# RA6M1_2.net
KiCad netlist of a schematic drawn in Altium Designer
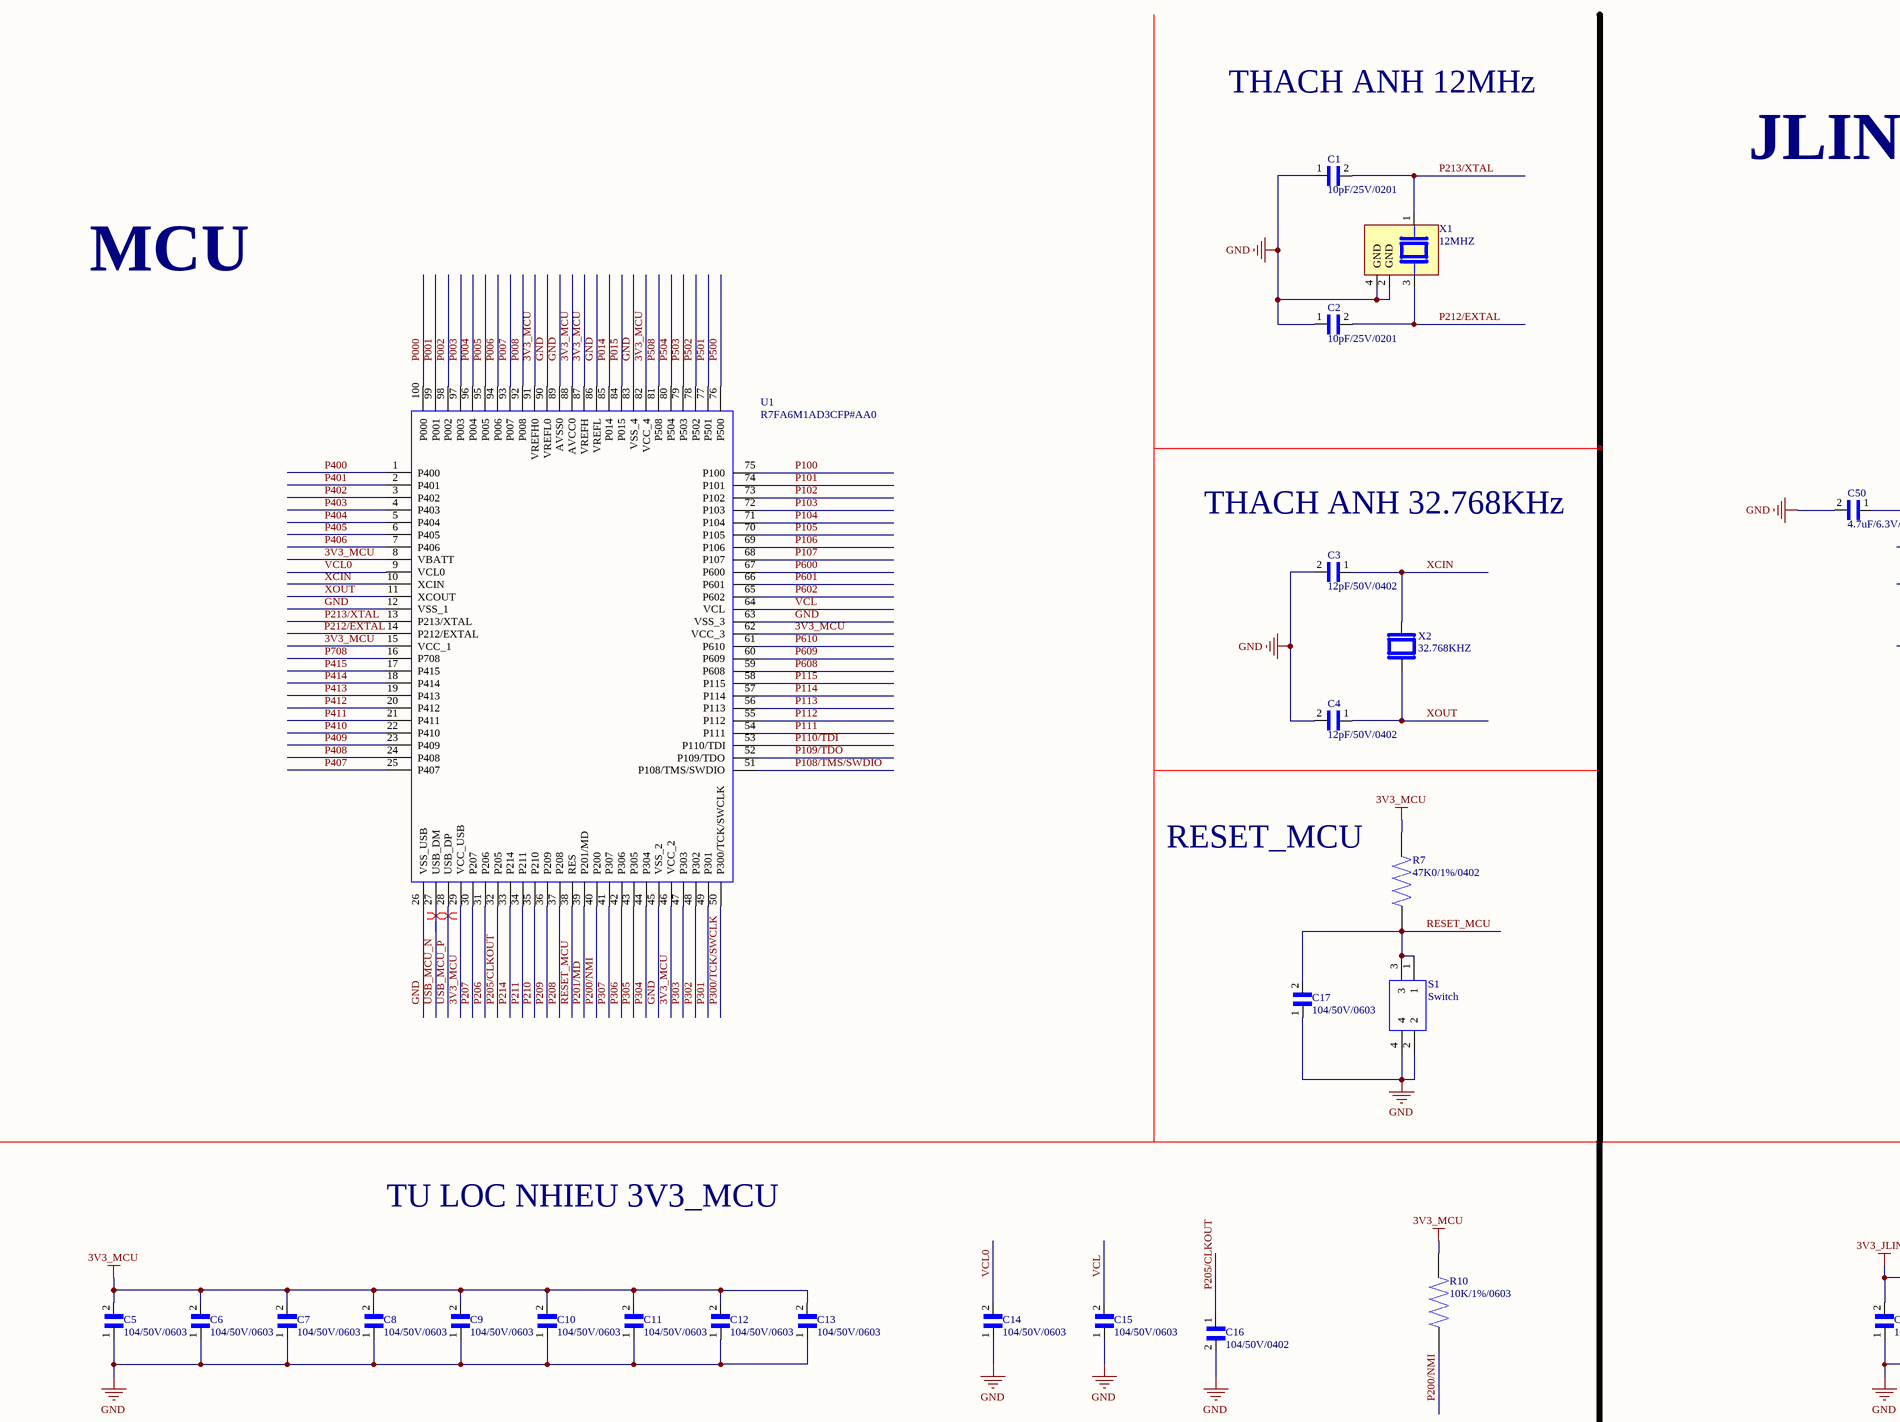
[diagram p0: RA6M1_2.SchDoc, top left]
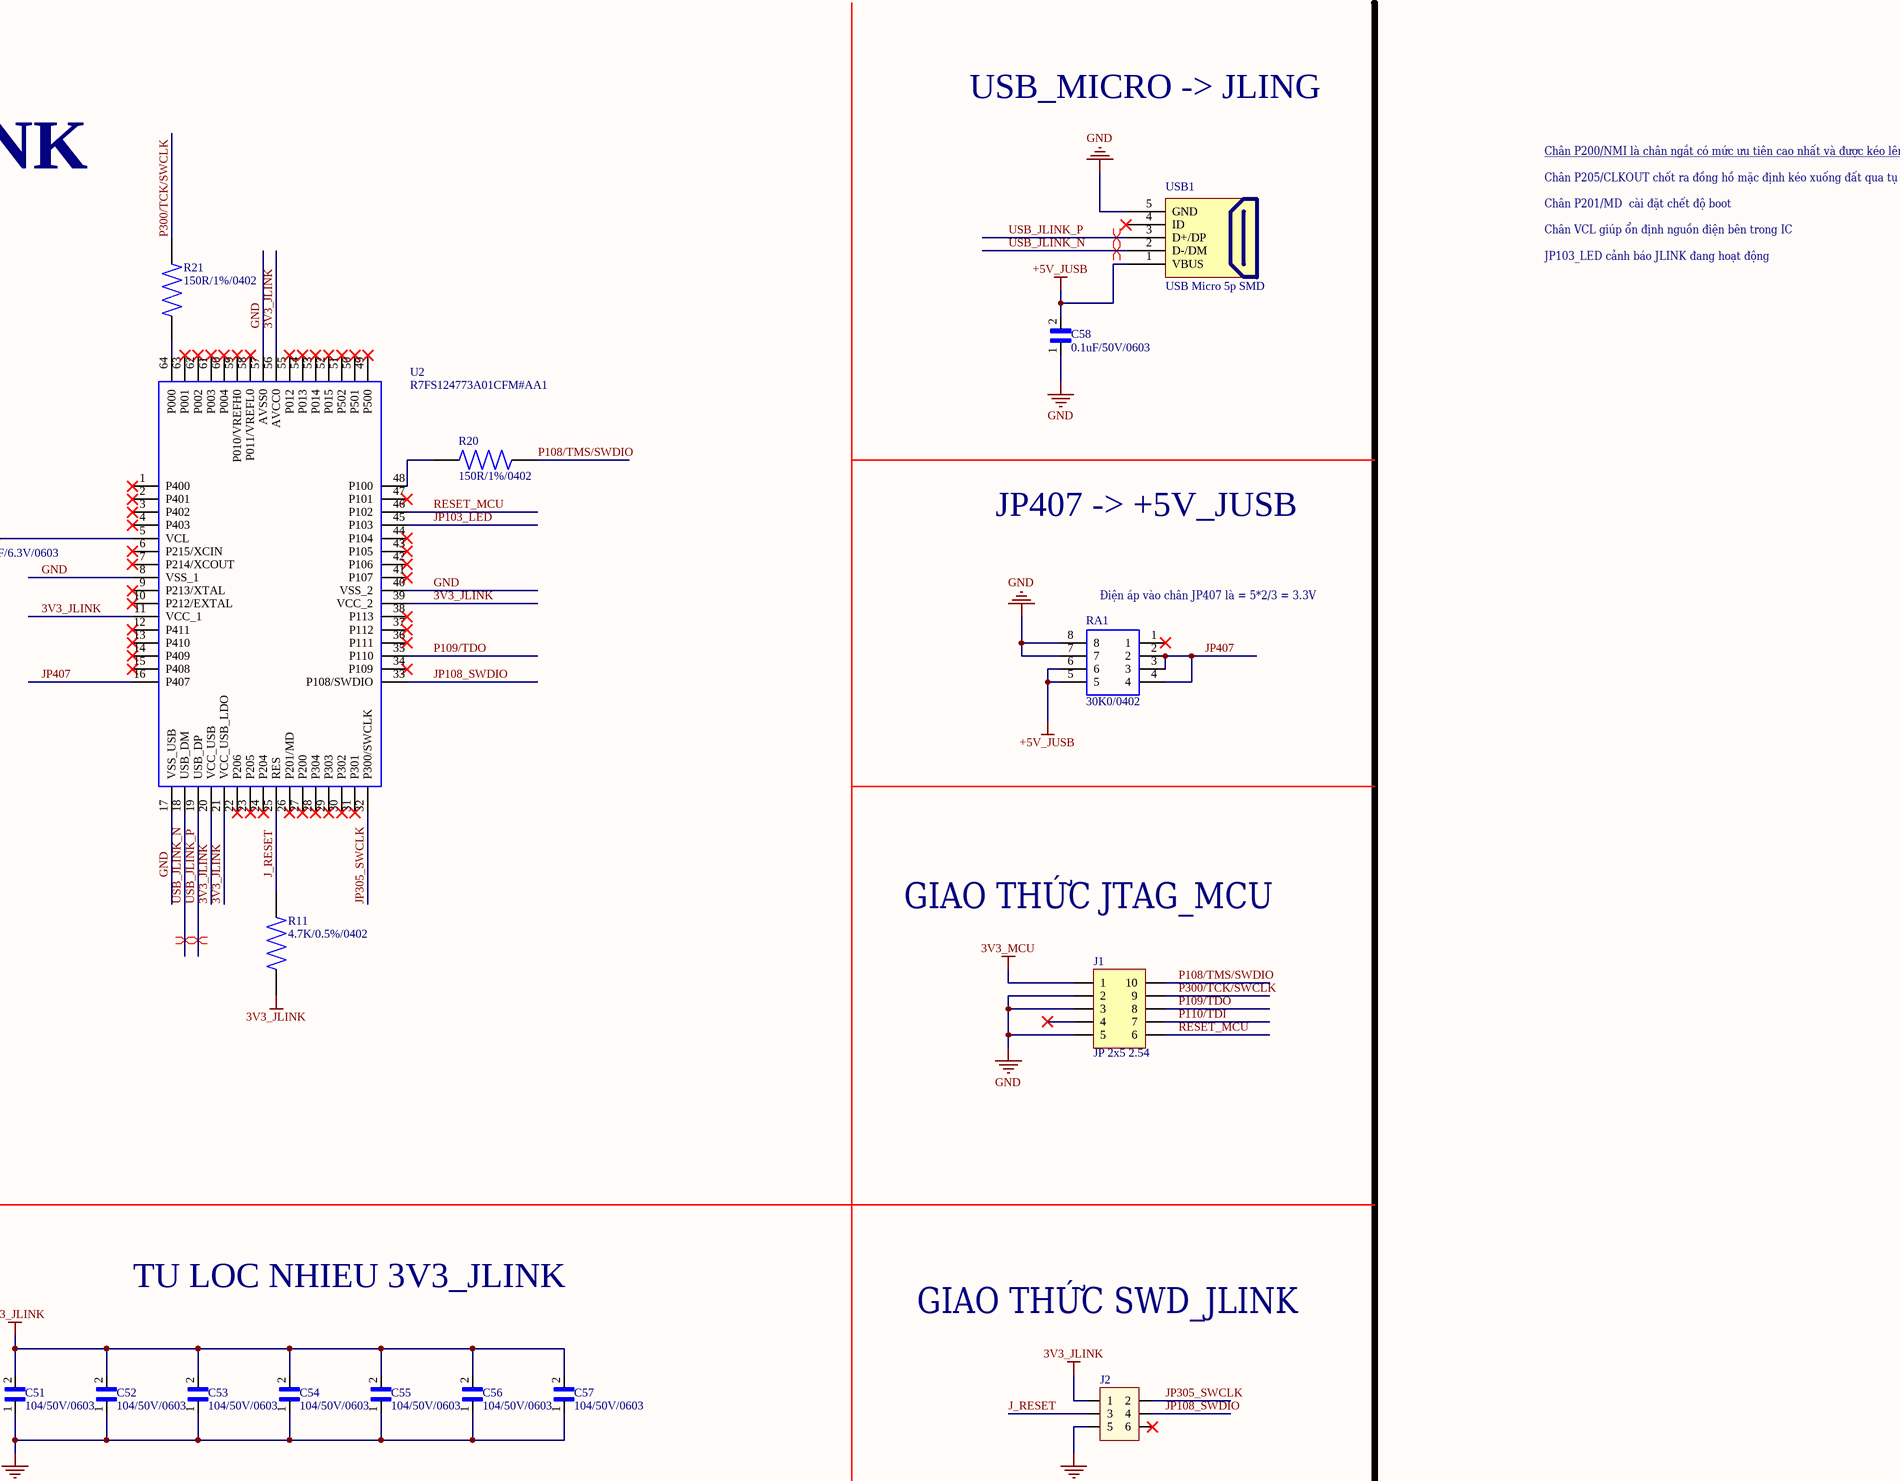
[diagram p1: RA6M1_2.SchDoc, top right]
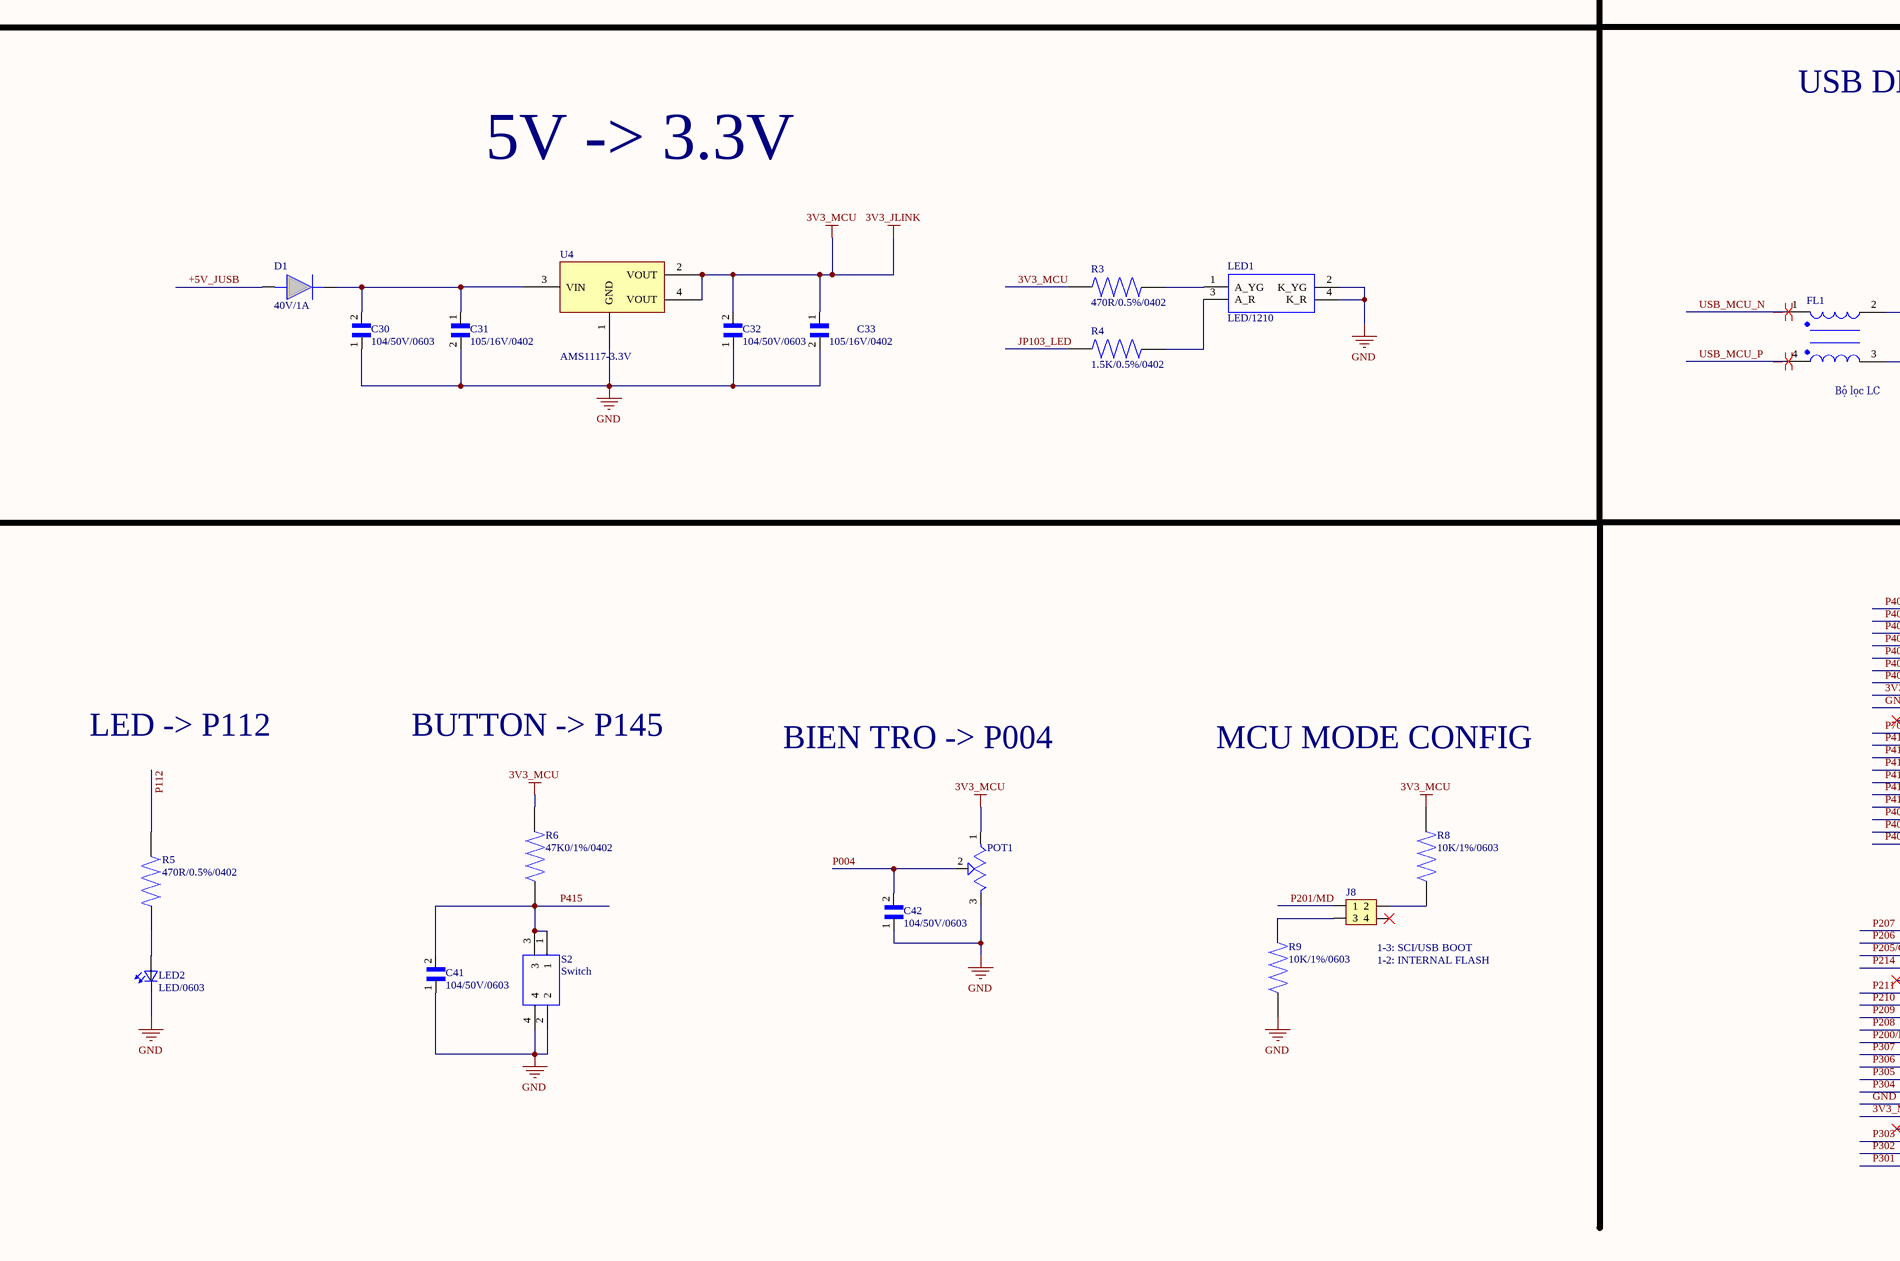
[diagram p2: RA6M1_2.SchDoc, bottom left]
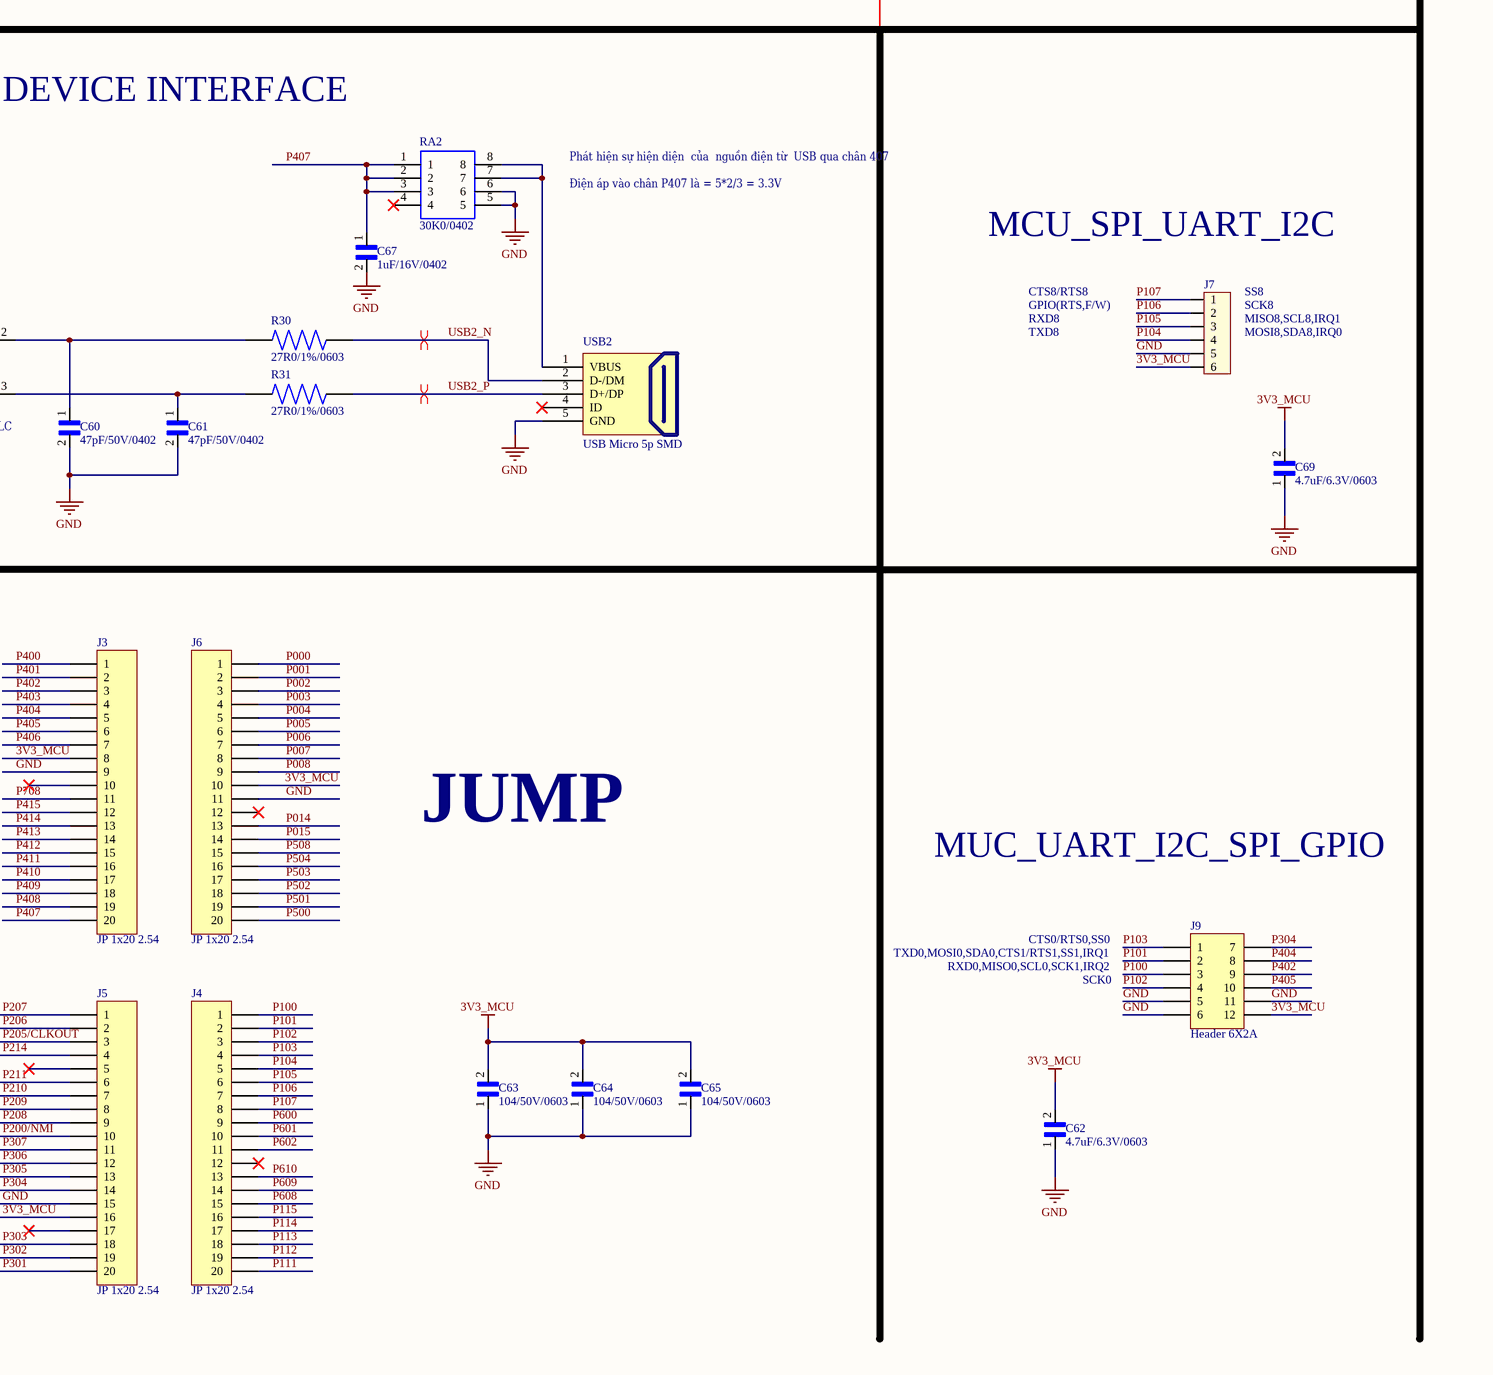
[diagram p3: RA6M1_2.SchDoc, bottom right]

(export (version "E")
  (design (tool "Eeschema 10.0.6"))
  (components
    (comp (ref "C1")
      (value "10pF/25V/0201")
      (footprint "RESC0603X26N")
      (description "TU0201")
      (fields (field (name "MP") "CL10B104KB8NNNC") (field (name "MF") "Samsung Electro-Mechanics"))
      (libsource (lib "Tu0201") (part "RESC0603X26N"))
    )
    (comp (ref "C2")
      (value "10pF/25V/0201")
      (footprint "RESC0603X26N")
      (description "TU0201")
      (fields (field (name "MP") "CL10B104KB8NNNC") (field (name "MF") "Samsung Electro-Mechanics"))
      (libsource (lib "Tu0201") (part "RESC0603X26N"))
    )
    (comp (ref "C3")
      (value "12pF/50V/0402")
      (footprint "CAPC1005X55N")
      (description "1ÂµF Â±10% 16V Ceramic Capacitor X5R 0402 (1005 Metric)")
      (fields (field (name "MP") "CL05A105KO5NNNC") (field (name "MF") "Samsung Electro-Mechanics"))
      (libsource (lib "RA6M1_DONE") (part "CL05A105KO5NNNC"))
    )
    (comp (ref "C4")
      (value "12pF/50V/0402")
      (footprint "CAPC1005X55N")
      (description "1ÂµF Â±10% 16V Ceramic Capacitor X5R 0402 (1005 Metric)")
      (fields (field (name "MP") "CL05A105KO5NNNC") (field (name "MF") "Samsung Electro-Mechanics"))
      (libsource (lib "RA6M1_DONE") (part "CL05A105KO5NNNC"))
    )
    (comp (ref "C5")
      (value "104/50V/0603")
      (footprint "CAPC1608X90N")
      (description "0.1ÂµF Â±10% 50V Ceramic Capacitor X7R 0603 _1608 Metric_")
      (fields (field (name "MP") "CL10B104KB8NNNC") (field (name "MF") "Samsung Electro-Mechanics"))
      (libsource (lib "RA6M1_DONE") (part "CL10B104KB8NNNC"))
    )
    (comp (ref "C6")
      (value "104/50V/0603")
      (footprint "CAPC1608X90N")
      (description "0.1ÂµF Â±10% 50V Ceramic Capacitor X7R 0603 _1608 Metric_")
      (fields (field (name "MP") "CL10B104KB8NNNC") (field (name "MF") "Samsung Electro-Mechanics"))
      (libsource (lib "RA6M1_DONE") (part "CL10B104KB8NNNC"))
    )
    (comp (ref "C7")
      (value "104/50V/0603")
      (footprint "CAPC1608X90N")
      (description "0.1ÂµF Â±10% 50V Ceramic Capacitor X7R 0603 _1608 Metric_")
      (fields (field (name "MP") "CL10B104KB8NNNC") (field (name "MF") "Samsung Electro-Mechanics"))
      (libsource (lib "RA6M1_DONE") (part "CL10B104KB8NNNC"))
    )
    (comp (ref "C8")
      (value "104/50V/0603")
      (footprint "CAPC1608X90N")
      (description "0.1ÂµF Â±10% 50V Ceramic Capacitor X7R 0603 _1608 Metric_")
      (fields (field (name "MP") "CL10B104KB8NNNC") (field (name "MF") "Samsung Electro-Mechanics"))
      (libsource (lib "RA6M1_DONE") (part "CL10B104KB8NNNC"))
    )
    (comp (ref "C9")
      (value "104/50V/0603")
      (footprint "CAPC1608X90N")
      (description "0.1ÂµF Â±10% 50V Ceramic Capacitor X7R 0603 _1608 Metric_")
      (fields (field (name "MP") "CL10B104KB8NNNC") (field (name "MF") "Samsung Electro-Mechanics"))
      (libsource (lib "RA6M1_DONE") (part "CL10B104KB8NNNC"))
    )
    (comp (ref "C10")
      (value "104/50V/0603")
      (footprint "CAPC1608X90N")
      (description "0.1ÂµF Â±10% 50V Ceramic Capacitor X7R 0603 _1608 Metric_")
      (fields (field (name "MP") "CL10B104KB8NNNC") (field (name "MF") "Samsung Electro-Mechanics"))
      (libsource (lib "RA6M1_DONE") (part "CL10B104KB8NNNC"))
    )
    (comp (ref "C11")
      (value "104/50V/0603")
      (footprint "CAPC1608X90N")
      (description "0.1ÂµF Â±10% 50V Ceramic Capacitor X7R 0603 _1608 Metric_")
      (fields (field (name "MP") "CL10B104KB8NNNC") (field (name "MF") "Samsung Electro-Mechanics"))
      (libsource (lib "RA6M1_DONE") (part "CL10B104KB8NNNC"))
    )
    (comp (ref "C12")
      (value "104/50V/0603")
      (footprint "CAPC1608X90N")
      (description "0.1ÂµF Â±10% 50V Ceramic Capacitor X7R 0603 _1608 Metric_")
      (fields (field (name "MP") "CL10B104KB8NNNC") (field (name "MF") "Samsung Electro-Mechanics"))
      (libsource (lib "RA6M1_DONE") (part "CL10B104KB8NNNC"))
    )
    (comp (ref "C13")
      (value "104/50V/0603")
      (footprint "CAPC1608X90N")
      (description "0.1ÂµF Â±10% 50V Ceramic Capacitor X7R 0603 _1608 Metric_")
      (fields (field (name "MP") "CL10B104KB8NNNC") (field (name "MF") "Samsung Electro-Mechanics"))
      (libsource (lib "RA6M1_DONE") (part "CL10B104KB8NNNC"))
    )
    (comp (ref "C14")
      (value "104/50V/0603")
      (footprint "CAPC1608X90N")
      (description "0.1ÂµF Â±10% 50V Ceramic Capacitor X7R 0603 _1608 Metric_")
      (fields (field (name "MP") "CL10B104KB8NNNC") (field (name "MF") "Samsung Electro-Mechanics"))
      (libsource (lib "RA6M1_DONE") (part "CL10B104KB8NNNC"))
    )
    (comp (ref "C15")
      (value "104/50V/0603")
      (footprint "CAPC1608X90N")
      (description "0.1ÂµF Â±10% 50V Ceramic Capacitor X7R 0603 _1608 Metric_")
      (fields (field (name "MP") "CL10B104KB8NNNC") (field (name "MF") "Samsung Electro-Mechanics"))
      (libsource (lib "RA6M1_DONE") (part "CL10B104KB8NNNC"))
    )
    (comp (ref "C16")
      (value "104/50V/0402")
      (footprint "CAPC1005X55N")
      (description "1ÂµF Â±10% 16V Ceramic Capacitor X5R 0402 (1005 Metric)")
      (fields (field (name "MP") "CL05A105KO5NNNC") (field (name "MF") "Samsung Electro-Mechanics"))
      (libsource (lib "") (part "CL05A105KO5NNNC_1"))
    )
    (comp (ref "C17")
      (value "104/50V/0603")
      (footprint "CAPC1608X90N")
      (description "0.1ÂµF Â±10% 50V Ceramic Capacitor X7R 0603 _1608 Metric_")
      (fields (field (name "MP") "CL10B104KB8NNNC") (field (name "MF") "Samsung Electro-Mechanics"))
      (libsource (lib "RA6M1_DONE") (part "CL10B104KB8NNNC"))
    )
    (comp (ref "C30")
      (value "104/50V/0603")
      (footprint "CAPC1608X90N")
      (description "0.1ÂµF Â±10% 50V Ceramic Capacitor X7R 0603 _1608 Metric_")
      (fields (field (name "MP") "CL10B104KB8NNNC") (field (name "MF") "Samsung Electro-Mechanics"))
      (libsource (lib "RA6M1_DONE") (part "CL10B104KB8NNNC"))
    )
    (comp (ref "C31")
      (value "105/16V/0402")
      (footprint "CAPC1005X55N")
      (description "1ÂµF Â±10% 16V Ceramic Capacitor X5R 0402 (1005 Metric)")
      (fields (field (name "MP") "CL05A105KO5NNNC") (field (name "MF") "Samsung Electro-Mechanics"))
      (libsource (lib "") (part "CL05A105KO5NNNC_1"))
    )
    (comp (ref "C32")
      (value "104/50V/0603")
      (footprint "CAPC1608X90N")
      (description "0.1ÂµF Â±10% 50V Ceramic Capacitor X7R 0603 _1608 Metric_")
      (fields (field (name "MP") "CL10B104KB8NNNC") (field (name "MF") "Samsung Electro-Mechanics"))
      (libsource (lib "RA6M1_DONE") (part "CL10B104KB8NNNC"))
    )
    (comp (ref "C33")
      (value "105/16V/0402")
      (footprint "CAPC1005X55N")
      (description "1ÂµF Â±10% 16V Ceramic Capacitor X5R 0402 (1005 Metric)")
      (fields (field (name "MP") "CL05A105KO5NNNC") (field (name "MF") "Samsung Electro-Mechanics"))
      (libsource (lib "") (part "CL05A105KO5NNNC_1"))
    )
    (comp (ref "C41")
      (value "104/50V/0603")
      (footprint "CAPC1608X90N")
      (description "0.1ÂµF Â±10% 50V Ceramic Capacitor X7R 0603 _1608 Metric_")
      (fields (field (name "MP") "CL10B104KB8NNNC") (field (name "MF") "Samsung Electro-Mechanics"))
      (libsource (lib "RA6M1_DONE") (part "CL10B104KB8NNNC"))
    )
    (comp (ref "C42")
      (value "104/50V/0603")
      (footprint "CAPC1608X90N")
      (description "0.1ÂµF Â±10% 50V Ceramic Capacitor X7R 0603 _1608 Metric_")
      (fields (field (name "MP") "CL10B104KB8NNNC") (field (name "MF") "Samsung Electro-Mechanics"))
      (libsource (lib "RA6M1_DONE") (part "CL10B104KB8NNNC"))
    )
    (comp (ref "C50")
      (value "4.7uF/6.3V/0603")
      (footprint "CAPC1608X90N")
      (description "0.1ÂµF Â±10% 50V Ceramic Capacitor X7R 0603 _1608 Metric_")
      (fields (field (name "MP") "CL10B104KB8NNNC") (field (name "MF") "Samsung Electro-Mechanics"))
      (libsource (lib "") (part "CL10B104KB8NNNC_1"))
    )
    (comp (ref "C51")
      (value "104/50V/0603")
      (footprint "CAPC1608X90N")
      (description "0.1ÂµF Â±10% 50V Ceramic Capacitor X7R 0603 _1608 Metric_")
      (fields (field (name "MP") "CL10B104KB8NNNC") (field (name "MF") "Samsung Electro-Mechanics"))
      (libsource (lib "RA6M1_DONE") (part "CL10B104KB8NNNC"))
    )
    (comp (ref "C52")
      (value "104/50V/0603")
      (footprint "CAPC1608X90N")
      (description "0.1ÂµF Â±10% 50V Ceramic Capacitor X7R 0603 _1608 Metric_")
      (fields (field (name "MP") "CL10B104KB8NNNC") (field (name "MF") "Samsung Electro-Mechanics"))
      (libsource (lib "RA6M1_DONE") (part "CL10B104KB8NNNC"))
    )
    (comp (ref "C53")
      (value "104/50V/0603")
      (footprint "CAPC1608X90N")
      (description "0.1ÂµF Â±10% 50V Ceramic Capacitor X7R 0603 _1608 Metric_")
      (fields (field (name "MP") "CL10B104KB8NNNC") (field (name "MF") "Samsung Electro-Mechanics"))
      (libsource (lib "RA6M1_DONE") (part "CL10B104KB8NNNC"))
    )
    (comp (ref "C54")
      (value "104/50V/0603")
      (footprint "CAPC1608X90N")
      (description "0.1ÂµF Â±10% 50V Ceramic Capacitor X7R 0603 _1608 Metric_")
      (fields (field (name "MP") "CL10B104KB8NNNC") (field (name "MF") "Samsung Electro-Mechanics"))
      (libsource (lib "RA6M1_DONE") (part "CL10B104KB8NNNC"))
    )
    (comp (ref "C55")
      (value "104/50V/0603")
      (footprint "CAPC1608X90N")
      (description "0.1ÂµF Â±10% 50V Ceramic Capacitor X7R 0603 _1608 Metric_")
      (fields (field (name "MP") "CL10B104KB8NNNC") (field (name "MF") "Samsung Electro-Mechanics"))
      (libsource (lib "RA6M1_DONE") (part "CL10B104KB8NNNC"))
    )
    (comp (ref "C56")
      (value "104/50V/0603")
      (footprint "CAPC1608X90N")
      (description "0.1ÂµF Â±10% 50V Ceramic Capacitor X7R 0603 _1608 Metric_")
      (fields (field (name "MP") "CL10B104KB8NNNC") (field (name "MF") "Samsung Electro-Mechanics"))
      (libsource (lib "RA6M1_DONE") (part "CL10B104KB8NNNC"))
    )
    (comp (ref "C57")
      (value "104/50V/0603")
      (footprint "CAPC1608X90N")
      (description "0.1ÂµF Â±10% 50V Ceramic Capacitor X7R 0603 _1608 Metric_")
      (fields (field (name "MP") "CL10B104KB8NNNC") (field (name "MF") "Samsung Electro-Mechanics"))
      (libsource (lib "RA6M1_DONE") (part "CL10B104KB8NNNC"))
    )
    (comp (ref "C58")
      (value "0.1uF/50V/0603")
      (footprint "CAPC1608X90N")
      (description "0.1ÂµF Â±10% 50V Ceramic Capacitor X7R 0603 _1608 Metric_")
      (fields (field (name "MP") "CL10B104KB8NNNC") (field (name "MF") "Samsung Electro-Mechanics"))
      (libsource (lib "RA6M1_DONE") (part "CL10B104KB8NNNC"))
    )
    (comp (ref "C60")
      (value "47pF/50V/0402")
      (footprint "CAPC1005X55N")
      (description "1ÂµF Â±10% 16V Ceramic Capacitor X5R 0402 (1005 Metric)")
      (fields (field (name "MP") "CL05A105KO5NNNC") (field (name "MF") "Samsung Electro-Mechanics"))
      (libsource (lib "") (part "CL05A105KO5NNNC_1"))
    )
    (comp (ref "C61")
      (value "47pF/50V/0402")
      (footprint "CAPC1005X55N")
      (description "1ÂµF Â±10% 16V Ceramic Capacitor X5R 0402 (1005 Metric)")
      (fields (field (name "MP") "CL05A105KO5NNNC") (field (name "MF") "Samsung Electro-Mechanics"))
      (libsource (lib "") (part "CL05A105KO5NNNC_1"))
    )
    (comp (ref "C62")
      (value "4.7uF/6.3V/0603")
      (footprint "CAPC1608X90N")
      (description "0.1ÂµF Â±10% 50V Ceramic Capacitor X7R 0603 _1608 Metric_")
      (fields (field (name "MP") "CL10B104KB8NNNC") (field (name "MF") "Samsung Electro-Mechanics"))
      (libsource (lib "RA6M1_DONE") (part "CL10B104KB8NNNC"))
    )
    (comp (ref "C63")
      (value "104/50V/0603")
      (footprint "CAPC1608X90N")
      (description "0.1ÂµF Â±10% 50V Ceramic Capacitor X7R 0603 _1608 Metric_")
      (fields (field (name "MP") "CL10B104KB8NNNC") (field (name "MF") "Samsung Electro-Mechanics"))
      (libsource (lib "RA6M1_DONE") (part "CL10B104KB8NNNC"))
    )
    (comp (ref "C64")
      (value "104/50V/0603")
      (footprint "CAPC1608X90N")
      (description "0.1ÂµF Â±10% 50V Ceramic Capacitor X7R 0603 _1608 Metric_")
      (fields (field (name "MP") "CL10B104KB8NNNC") (field (name "MF") "Samsung Electro-Mechanics"))
      (libsource (lib "RA6M1_DONE") (part "CL10B104KB8NNNC"))
    )
    (comp (ref "C65")
      (value "104/50V/0603")
      (footprint "CAPC1608X90N")
      (description "0.1ÂµF Â±10% 50V Ceramic Capacitor X7R 0603 _1608 Metric_")
      (fields (field (name "MP") "CL10B104KB8NNNC") (field (name "MF") "Samsung Electro-Mechanics"))
      (libsource (lib "RA6M1_DONE") (part "CL10B104KB8NNNC"))
    )
    (comp (ref "C67")
      (value "1uF/16V/0402")
      (footprint "CAPC1005X55N")
      (description "1ÂµF Â±10% 16V Ceramic Capacitor X5R 0402 (1005 Metric)")
      (fields (field (name "MP") "CL05A105KO5NNNC") (field (name "MF") "Samsung Electro-Mechanics"))
      (libsource (lib "") (part "CL05A105KO5NNNC_1"))
    )
    (comp (ref "C69")
      (value "4.7uF/6.3V/0603")
      (footprint "CAPC1608X90N")
      (description "0.1ÂµF Â±10% 50V Ceramic Capacitor X7R 0603 _1608 Metric_")
      (fields (field (name "MP") "CL10B104KB8NNNC") (field (name "MF") "Samsung Electro-Mechanics"))
      (libsource (lib "RA6M1_DONE") (part "CL10B104KB8NNNC"))
    )
    (comp (ref "D1")
      (value "40V/1A")
      (footprint "SODFL3616X98N")
      (fields
        (field (name "MANUFACTURER_PART_NUMBER") "MBR140SFT1G")
        (field (name "MOUSER PART NUMBER") "863-MBR140SFT1G")
      )
      (libsource (lib "RA6M1_DONE") (part "MBR140SFT1G"))
    )
    (comp (ref "FL1")
      (value "DLP11SN201HL2L")
      (footprint "FIL_DLP11SN201HL2L")
      (description "2 Line Common Mode Choke Surface Mount 200 Ohms @ 100MHz 110mA DCR 3.88Ohm")
      (fields (field (name "MF") "Murata"))
      (libsource (lib "RA6M1_DONE") (part "DLP11SN201HL2L"))
    )
    (comp (ref "J1")
      (value "JP 2x5 2.54")
      (footprint "JP 2x5 DT")
      (description "Cắm")
      (libsource (lib "Altium_Lib_by_KhueNguyenCreator") (part "JP 2x5 2.54 Duc Thang"))
    )
    (comp (ref "J2")
      (value "HEAD 3x2")
      (footprint "HDR2X3")
      (description "Connector 3x2")
      (libsource (lib "My library altium") (part "JP3x2"))
    )
    (comp (ref "J3")
      (value "JP 1x20 2.54")
      (footprint "JP 1x20 DT")
      (description "Cắm")
      (libsource (lib "Altium_Lib_by_KhueNguyenCreator") (part "JP 1x20 2.54 Duc Thang"))
    )
    (comp (ref "J4")
      (value "JP 1x20 2.54")
      (footprint "JP 1x20 DT")
      (description "Cắm")
      (libsource (lib "") (part "JP 1x20 2.54 Duc Thang_1"))
    )
    (comp (ref "J5")
      (value "JP 1x20 2.54")
      (footprint "JP 1x20 DT")
      (description "Cắm")
      (libsource (lib "Altium_Lib_by_KhueNguyenCreator") (part "JP 1x20 2.54 Duc Thang"))
    )
    (comp (ref "J6")
      (value "JP 1x20 2.54")
      (footprint "JP 1x20 DT")
      (description "Cắm")
      (libsource (lib "") (part "JP 1x20 2.54 Duc Thang_1"))
    )
    (comp (ref "J7")
      (value "JP6")
      (footprint "jam6")
      (description "jam 6")
      (libsource (lib "My library altium") (part "jam 6"))
    )
    (comp (ref "J8")
      (value "JP2x2")
      (footprint "HDR2X2")
      (libsource (lib "My library altium") (part "JP2x2"))
    )
    (comp (ref "J9")
      (value "Header 6X2A")
      (footprint "HDR2X6_CEN")
      (description "Header, 6-Pin, Dual row")
      (fields (field (name "PUBLISHER") "Altium Limited"))
      (libsource (lib "My library altium") (part "Header 6X2A"))
    )
    (comp (ref "LED1")
      (value "LED/1210")
      (footprint "LED_597-7701-507F")
      (description "Standard LEDs - SMD Red/Green WC 80/50mcd 645/570nm")
      (fields
        (field (name "MANUFACTURER_PART_NUMBER") "598-8610-207F")
        (field (name "MOUSER PART NUMBER") "645-598-8610-207F")
      )
      (libsource (lib "RA6M1_DONE") (part "598-8610-207F"))
    )
    (comp (ref "LED2")
      (value "LED/0603")
      (footprint "0603")
      (description "http://octopart.com/ltst-c190krkt-lite-on-549893")
      (fields (field (name "MP") "LTST-C191KRKT"))
      (libsource (lib "RA6M1_DONE") (part "LTST-C191KRKT"))
    )
    (comp (ref "POT1")
      (value "10K0")
      (footprint "TRIM_3352T-1-103LF")
      (description "10 kOhms 0.5W, 1/2W Through Hole Thumbwheel Potentiometer Top Adjustment")
      (fields (field (name "MP") "3352T-1-103LF") (field (name "MF") "Bourns"))
      (libsource (lib "RA6M1_DONE") (part "3352T-1-103LF"))
    )
    (comp (ref "R3")
      (value "470R/0.5%/0402")
      (footprint "RES_ERA2AED472X")
      (description "Res Thin Film 0402 4.7K Ohm 0.5% 0.063W(1/16W) 25ppm/C Molded SMD Automotive Punched T/R")
      (fields (field (name "MF") "Panasonic Electronic") (field (name "MP") "ERA-2AED472X"))
      (libsource (lib "RA6M1_DONE") (part "ERA2AED472X"))
    )
    (comp (ref "R4")
      (value "1.5K/0.5%/0402")
      (footprint "RES_ERA2AED472X")
      (description "Res Thin Film 0402 4.7K Ohm 0.5% 0.063W(1/16W) 25ppm/C Molded SMD Automotive Punched T/R")
      (fields (field (name "MF") "Panasonic Electronic") (field (name "MP") "ERA-2AED472X"))
      (libsource (lib "RA6M1_DONE") (part "ERA2AED472X"))
    )
    (comp (ref "R5")
      (value "470R/0.5%/0402")
      (footprint "RES_ERA2AED472X")
      (description "Res Thin Film 0402 4.7K Ohm 0.5% 0.063W(1/16W) 25ppm/C Molded SMD Automotive Punched T/R")
      (fields (field (name "MF") "Panasonic Electronic") (field (name "MP") "ERA-2AED472X"))
      (libsource (lib "RA6M1_DONE") (part "ERA2AED472X"))
    )
    (comp (ref "R6")
      (value "47K0/1%/0402")
      (footprint "RES_ERA2AED472X")
      (description "Res Thin Film 0402 4.7K Ohm 0.5% 0.063W(1/16W) 25ppm/C Molded SMD Automotive Punched T/R")
      (fields (field (name "MF") "Panasonic Electronic") (field (name "MP") "ERA-2AED472X"))
      (libsource (lib "RA6M1_DONE") (part "ERA2AED472X"))
    )
    (comp (ref "R7")
      (value "47K0/1%/0402")
      (footprint "RES_ERA2AED472X")
      (description "Res Thin Film 0402 4.7K Ohm 0.5% 0.063W(1/16W) 25ppm/C Molded SMD Automotive Punched T/R")
      (fields (field (name "MF") "Panasonic Electronic") (field (name "MP") "ERA-2AED472X"))
      (libsource (lib "RA6M1_DONE") (part "ERA2AED472X"))
    )
    (comp (ref "R8")
      (value "10K/1%/0603")
      (footprint "RESC1508X55N")
      (fields (field (name "MP") "RMCF0603JT27R0"))
      (libsource (lib "RA6M1_DONE") (part "RMCF0603JT27R0"))
    )
    (comp (ref "R9")
      (value "10K/1%/0603")
      (footprint "RESC1508X55N")
      (fields (field (name "MP") "RMCF0603JT27R0"))
      (libsource (lib "RA6M1_DONE") (part "RMCF0603JT27R0"))
    )
    (comp (ref "R10")
      (value "10K/1%/0603")
      (footprint "RESC1508X55N")
      (fields (field (name "MP") "RMCF0603JT27R0"))
      (libsource (lib "RA6M1_DONE") (part "RMCF0603JT27R0"))
    )
    (comp (ref "R11")
      (value "4.7K/0.5%/0402")
      (footprint "RES_ERA2AED472X")
      (description "Res Thin Film 0402 4.7K Ohm 0.5% 0.063W(1/16W) 25ppm/C Molded SMD Automotive Punched T/R")
      (fields (field (name "MF") "Panasonic Electronic") (field (name "MP") "ERA-2AED472X"))
      (libsource (lib "RA6M1_DONE") (part "ERA2AED472X"))
    )
    (comp (ref "R20")
      (value "150R/1%/0402")
      (footprint "RES_ERA2AED472X")
      (description "Res Thin Film 0402 4.7K Ohm 0.5% 0.063W(1/16W) 25ppm/C Molded SMD Automotive Punched T/R")
      (fields (field (name "MF") "Panasonic Electronic") (field (name "MP") "ERA-2AED472X"))
      (libsource (lib "RA6M1_DONE") (part "ERA2AED472X"))
    )
    (comp (ref "R21")
      (value "150R/1%/0402")
      (footprint "RES_ERA2AED472X")
      (description "Res Thin Film 0402 4.7K Ohm 0.5% 0.063W(1/16W) 25ppm/C Molded SMD Automotive Punched T/R")
      (fields (field (name "MF") "Panasonic Electronic") (field (name "MP") "ERA-2AED472X"))
      (libsource (lib "RA6M1_DONE") (part "ERA2AED472X"))
    )
    (comp (ref "R30")
      (value "27R0/1%/0603")
      (footprint "RESC1508X55N")
      (fields (field (name "MP") "RMCF0603JT27R0"))
      (libsource (lib "RA6M1_DONE") (part "RMCF0603JT27R0"))
    )
    (comp (ref "R31")
      (value "27R0/1%/0603")
      (footprint "RESC1508X55N")
      (fields (field (name "MP") "RMCF0603JT27R0"))
      (libsource (lib "RA6M1_DONE") (part "RMCF0603JT27R0"))
    )
    (comp (ref "RA1")
      (value "30K0/0402")
      (footprint "EXB28V510JX")
      (description "Resistor Networks & Arrays Resistor ArrayChip 0804 4 elements")
      (fields (field (name "MANUFACTURER_PART_NUMBER") "EXB28V303JX"))
      (libsource (lib "RA6M1_DONE") (part "EXB28V303JX"))
    )
    (comp (ref "RA2")
      (value "30K0/0402")
      (footprint "EXB28V510JX")
      (description "Resistor Networks & Arrays Resistor ArrayChip 0804 4 elements")
      (fields (field (name "MANUFACTURER_PART_NUMBER") "EXB28V303JX"))
      (libsource (lib "RA6M1_DONE") (part "EXB28V303JX"))
    )
    (comp (ref "S1")
      (value "Switch")
      (footprint "PTS645(SMT)")
      (description "C & K COMPONENTS - PTS645SM43SMTR92LFS - SWITCH, SPST, 0.05A, 12VDC, SMD, 4.3MM")
      (fields
        (field (name "MANUFACTURER_PART_NUMBER") "PTS645SM43SMTR92LFS")
        (field (name "MOUSER PART NUMBER") "611-PTS645SM43SMTR92")
      )
      (libsource (lib "RA6M1_DONE") (part "PTS645SM43SMTR92LFS"))
    )
    (comp (ref "S2")
      (value "Switch")
      (footprint "PTS645(SMT)")
      (description "C & K COMPONENTS - PTS645SM43SMTR92LFS - SWITCH, SPST, 0.05A, 12VDC, SMD, 4.3MM")
      (fields
        (field (name "MANUFACTURER_PART_NUMBER") "PTS645SM43SMTR92LFS")
        (field (name "MOUSER PART NUMBER") "611-PTS645SM43SMTR92")
      )
      (libsource (lib "RA6M1_DONE") (part "PTS645SM43SMTR92LFS"))
    )
    (comp (ref "U1")
      (value "R7FA6M1AD3CFP#AA0")
      (footprint "QFP50P1600X1600X170-100N")
      (description "ARM Cortex-M4 RA6M1 Microcontroller IC 32-Bit 120MHz 512KB (512K x 8) FLASH 100-LFQFP (14x14)")
      (fields (field (name "MOUSER PART NUMBER") "968-7FA6M1AD3CFP#AA0"))
      (libsource (lib "RA6M1_DONE") (part "R7FA6M1AD3CFP#AA0"))
    )
    (comp (ref "U2")
      (value "R7FS124773A01CFM#AA1")
      (footprint "QFP50P1200X1200X170-64N")
      (description "S124")
      (fields (field (name "MOUSER PART NUMBER") "968-124773A01CFM#AA1"))
      (libsource (lib "RA6M1_DONE") (part "R7FS124773A01CFM#AA1"))
    )
    (comp (ref "U4")
      (value "AMS1117-3.3V")
      (footprint "SOT223")
      (description "Dán")
      (libsource (lib "Altium_Lib_by_KhueNguyenCreator") (part "AMS1117 SMD"))
    )
    (comp (ref "USB1")
      (value "USB Micro 5p SMD")
      (footprint "USB Micro 5p SMD")
      (description "USB Type B")
      (libsource (lib "Altium_Lib_by_KhueNguyenCreator") (part "USB Micro 5p SMD"))
    )
    (comp (ref "USB2")
      (value "USB Micro 5p SMD")
      (footprint "USB Micro 5p SMD")
      (description "USB Type B")
      (libsource (lib "") (part "USB Micro 5p SMD_1"))
    )
    (comp (ref "X1")
      (value "12MHZ")
      (footprint "XTAL_ABM8G-12.000MHZ-B4Y-T")
      (description "12 MHz Â±30ppm Crystal 10pF 120 Ohms 4-SMD, No Lead")
      (fields (field (name "MP") "ABM8G-12.000MHZ-B4Y-T") (field (name "MF") "Abracon"))
      (libsource (lib "RA6M1_DONE") (part "ABM8G-12.000MHZ-B4Y-T"))
    )
    (comp (ref "X2")
      (value "32.768KHZ")
      (footprint "XTAL_ABS07-32.768KHZ-T")
      (description "32.768 kHz Â±20ppm Crystal 12.5pF 70 kOhms 2-SMD, No Lead")
      (fields (field (name "MP") "ABS07-32.768KHZ-T") (field (name "MF") "Abracon"))
      (libsource (lib "RA6M1_DONE") (part "ABS07-32.768KHZ-T"))
    )
  )
  (nets
    (net (code "1") (name "+5V_JUSB") (class "Default")
      (node (ref "C58") (pin "2") (pinfunction "2_2") (pintype "passive"))
      (node (ref "D1") (pin "2") (pinfunction "A_2") (pintype "passive"))
      (node (ref "RA1") (pin "5") (pinfunction "5_5") (pintype "passive"))
      (node (ref "RA1") (pin "6") (pinfunction "6_6") (pintype "passive"))
      (node (ref "USB1") (pin "1") (pinfunction "VBUS_1") (pintype "passive"))
    )
    (net (code "2") (name "/JP103_LED") (class "Default")
      (node (ref "R4") (pin "1") (pinfunction "1_1") (pintype "passive"))
      (node (ref "U2") (pin "45") (pinfunction "P103_45") (pintype "passive"))
    )
    (net (code "3") (name "/JP108_SWDIO") (class "Default")
      (node (ref "J2") (pin "4") (pinfunction "4_4") (pintype "passive"))
      (node (ref "U2") (pin "33") (pinfunction "P108/SWDIO_33") (pintype "passive"))
    )
    (net (code "4") (name "/JP305_SWCLK") (class "Default")
      (node (ref "J2") (pin "2") (pinfunction "2_2") (pintype "passive"))
      (node (ref "U2") (pin "32") (pinfunction "P300/SWCLK_32") (pintype "passive"))
    )
    (net (code "5") (name "/JP407") (class "Default")
      (node (ref "RA1") (pin "2") (pinfunction "2_2") (pintype "passive"))
      (node (ref "RA1") (pin "3") (pinfunction "3_3") (pintype "passive"))
      (node (ref "RA1") (pin "4") (pinfunction "4_4") (pintype "passive"))
      (node (ref "U2") (pin "16") (pinfunction "P407_16") (pintype "passive"))
    )
    (net (code "6") (name "/J_RESET") (class "Default")
      (node (ref "J2") (pin "3") (pinfunction "3_3") (pintype "passive"))
      (node (ref "R11") (pin "1") (pinfunction "1_1") (pintype "passive"))
      (node (ref "U2") (pin "25") (pinfunction "RES_25") (pintype "passive"))
    )
    (net (code "7") (name "/P000") (class "Default")
      (node (ref "J6") (pin "1") (pinfunction "1_1") (pintype "passive"))
      (node (ref "U1") (pin "100") (pinfunction "P000_100") (pintype "passive"))
    )
    (net (code "8") (name "/P001") (class "Default")
      (node (ref "J6") (pin "2") (pinfunction "2_2") (pintype "passive"))
      (node (ref "U1") (pin "99") (pinfunction "P001_99") (pintype "passive"))
    )
    (net (code "9") (name "/P002") (class "Default")
      (node (ref "J6") (pin "3") (pinfunction "3_3") (pintype "passive"))
      (node (ref "U1") (pin "98") (pinfunction "P002_98") (pintype "passive"))
    )
    (net (code "10") (name "/P003") (class "Default")
      (node (ref "J6") (pin "4") (pinfunction "4_4") (pintype "passive"))
      (node (ref "U1") (pin "97") (pinfunction "P003_97") (pintype "passive"))
    )
    (net (code "11") (name "/P004") (class "Default")
      (node (ref "C42") (pin "2") (pinfunction "2_2") (pintype "passive"))
      (node (ref "J6") (pin "5") (pinfunction "5_5") (pintype "passive"))
      (node (ref "POT1") (pin "2") (pinfunction "WIPER_2") (pintype "passive"))
      (node (ref "U1") (pin "96") (pinfunction "P004_96") (pintype "passive"))
    )
    (net (code "12") (name "/P005") (class "Default")
      (node (ref "J6") (pin "6") (pinfunction "6_6") (pintype "passive"))
      (node (ref "U1") (pin "95") (pinfunction "P005_95") (pintype "passive"))
    )
    (net (code "13") (name "/P006") (class "Default")
      (node (ref "J6") (pin "7") (pinfunction "7_7") (pintype "passive"))
      (node (ref "U1") (pin "94") (pinfunction "P006_94") (pintype "passive"))
    )
    (net (code "14") (name "/P007") (class "Default")
      (node (ref "J6") (pin "8") (pinfunction "8_8") (pintype "passive"))
      (node (ref "U1") (pin "93") (pinfunction "P007_93") (pintype "passive"))
    )
    (net (code "15") (name "/P008") (class "Default")
      (node (ref "J6") (pin "9") (pinfunction "9_9") (pintype "passive"))
      (node (ref "U1") (pin "92") (pinfunction "P008_92") (pintype "passive"))
    )
    (net (code "16") (name "/P014") (class "Default")
      (node (ref "J6") (pin "13") (pinfunction "13_13") (pintype "passive"))
      (node (ref "U1") (pin "85") (pinfunction "P014_85") (pintype "passive"))
    )
    (net (code "17") (name "/P015") (class "Default")
      (node (ref "J6") (pin "14") (pinfunction "14_14") (pintype "passive"))
      (node (ref "U1") (pin "84") (pinfunction "P015_84") (pintype "passive"))
    )
    (net (code "18") (name "/P100") (class "Default")
      (node (ref "J4") (pin "1") (pinfunction "1_1") (pintype "passive"))
      (node (ref "J9") (pin "3") (pinfunction "3_3") (pintype "passive"))
      (node (ref "U1") (pin "75") (pinfunction "P100_75") (pintype "passive"))
    )
    (net (code "19") (name "/P101") (class "Default")
      (node (ref "J4") (pin "2") (pinfunction "2_2") (pintype "passive"))
      (node (ref "J9") (pin "2") (pinfunction "2_2") (pintype "passive"))
      (node (ref "U1") (pin "74") (pinfunction "P101_74") (pintype "passive"))
    )
    (net (code "20") (name "/P102") (class "Default")
      (node (ref "J4") (pin "3") (pinfunction "3_3") (pintype "passive"))
      (node (ref "J9") (pin "4") (pinfunction "4_4") (pintype "passive"))
      (node (ref "U1") (pin "73") (pinfunction "P102_73") (pintype "passive"))
    )
    (net (code "21") (name "/P103") (class "Default")
      (node (ref "J4") (pin "4") (pinfunction "4_4") (pintype "passive"))
      (node (ref "J9") (pin "1") (pinfunction "1_1") (pintype "passive"))
      (node (ref "U1") (pin "72") (pinfunction "P103_72") (pintype "passive"))
    )
    (net (code "22") (name "/P104") (class "Default")
      (node (ref "J4") (pin "5") (pinfunction "5_5") (pintype "passive"))
      (node (ref "J7") (pin "4") (pinfunction "4_4") (pintype "passive"))
      (node (ref "U1") (pin "71") (pinfunction "P104_71") (pintype "passive"))
    )
    (net (code "23") (name "/P105") (class "Default")
      (node (ref "J4") (pin "6") (pinfunction "6_6") (pintype "passive"))
      (node (ref "J7") (pin "3") (pinfunction "3_3") (pintype "passive"))
      (node (ref "U1") (pin "70") (pinfunction "P105_70") (pintype "passive"))
    )
    (net (code "24") (name "/P106") (class "Default")
      (node (ref "J4") (pin "7") (pinfunction "7_7") (pintype "passive"))
      (node (ref "J7") (pin "2") (pinfunction "2_2") (pintype "passive"))
      (node (ref "U1") (pin "69") (pinfunction "P106_69") (pintype "passive"))
    )
    (net (code "25") (name "/P107") (class "Default")
      (node (ref "J4") (pin "8") (pinfunction "8_8") (pintype "passive"))
      (node (ref "J7") (pin "1") (pinfunction "1_1") (pintype "passive"))
      (node (ref "U1") (pin "68") (pinfunction "P107_68") (pintype "passive"))
    )
    (net (code "26") (name "/P108{slash}TMS{slash}SWDIO") (class "Default")
      (node (ref "J1") (pin "10") (pinfunction "10_10") (pintype "passive"))
      (node (ref "R20") (pin "2") (pinfunction "2_2") (pintype "passive"))
      (node (ref "U1") (pin "51") (pinfunction "P108/TMS/SWDIO_51") (pintype "passive"))
    )
    (net (code "27") (name "/P109{slash}TDO") (class "Default")
      (node (ref "J1") (pin "8") (pinfunction "8_8") (pintype "passive"))
      (node (ref "U1") (pin "52") (pinfunction "P109/TDO_52") (pintype "passive"))
      (node (ref "U2") (pin "35") (pinfunction "P110_35") (pintype "passive"))
    )
    (net (code "28") (name "/P110{slash}TDI") (class "Default")
      (node (ref "J1") (pin "7") (pinfunction "7_7") (pintype "passive"))
      (node (ref "U1") (pin "53") (pinfunction "P110/TDI_53") (pintype "passive"))
    )
    (net (code "29") (name "/P111") (class "Default")
      (node (ref "J4") (pin "20") (pinfunction "20_20") (pintype "passive"))
      (node (ref "U1") (pin "54") (pinfunction "P111_54") (pintype "passive"))
    )
    (net (code "30") (name "/P112") (class "Default")
      (node (ref "J4") (pin "19") (pinfunction "19_19") (pintype "passive"))
      (node (ref "R5") (pin "1") (pinfunction "1_1") (pintype "passive"))
      (node (ref "U1") (pin "55") (pinfunction "P112_55") (pintype "passive"))
    )
    (net (code "31") (name "/P113") (class "Default")
      (node (ref "J4") (pin "18") (pinfunction "18_18") (pintype "passive"))
      (node (ref "U1") (pin "56") (pinfunction "P113_56") (pintype "passive"))
    )
    (net (code "32") (name "/P114") (class "Default")
      (node (ref "J4") (pin "17") (pinfunction "17_17") (pintype "passive"))
      (node (ref "U1") (pin "57") (pinfunction "P114_57") (pintype "passive"))
    )
    (net (code "33") (name "/P115") (class "Default")
      (node (ref "J4") (pin "16") (pinfunction "16_16") (pintype "passive"))
      (node (ref "U1") (pin "58") (pinfunction "P115_58") (pintype "passive"))
    )
    (net (code "34") (name "/P200{slash}NMI") (class "Default")
      (node (ref "J5") (pin "10") (pinfunction "10_10") (pintype "passive"))
      (node (ref "R10") (pin "1") (pinfunction "1_1") (pintype "passive"))
      (node (ref "U1") (pin "40") (pinfunction "P200_40") (pintype "passive"))
    )
    (net (code "35") (name "/P201{slash}MD") (class "Default")
      (node (ref "J8") (pin "1") (pinfunction "1_1") (pintype "passive"))
      (node (ref "U1") (pin "39") (pinfunction "P201/MD_39") (pintype "passive"))
    )
    (net (code "36") (name "/P205{slash}CLKOUT") (class "Default")
      (node (ref "C16") (pin "1") (pinfunction "1_1") (pintype "passive"))
      (node (ref "J5") (pin "3") (pinfunction "3_3") (pintype "passive"))
      (node (ref "U1") (pin "32") (pinfunction "P205_32") (pintype "passive"))
    )
    (net (code "37") (name "/P206") (class "Default")
      (node (ref "J5") (pin "2") (pinfunction "2_2") (pintype "passive"))
      (node (ref "U1") (pin "31") (pinfunction "P206_31") (pintype "passive"))
    )
    (net (code "38") (name "/P207") (class "Default")
      (node (ref "J5") (pin "1") (pinfunction "1_1") (pintype "passive"))
      (node (ref "U1") (pin "30") (pinfunction "P207_30") (pintype "passive"))
    )
    (net (code "39") (name "/P208") (class "Default")
      (node (ref "J5") (pin "9") (pinfunction "9_9") (pintype "passive"))
      (node (ref "U1") (pin "37") (pinfunction "P208_37") (pintype "passive"))
    )
    (net (code "40") (name "/P209") (class "Default")
      (node (ref "J5") (pin "8") (pinfunction "8_8") (pintype "passive"))
      (node (ref "U1") (pin "36") (pinfunction "P209_36") (pintype "passive"))
    )
    (net (code "41") (name "/P210") (class "Default")
      (node (ref "J5") (pin "7") (pinfunction "7_7") (pintype "passive"))
      (node (ref "U1") (pin "35") (pinfunction "P210_35") (pintype "passive"))
    )
    (net (code "42") (name "/P211") (class "Default")
      (node (ref "J5") (pin "6") (pinfunction "6_6") (pintype "passive"))
      (node (ref "U1") (pin "34") (pinfunction "P211_34") (pintype "passive"))
    )
    (net (code "43") (name "/P212{slash}EXTAL") (class "Default")
      (node (ref "C2") (pin "2") (pinfunction "2_2") (pintype "passive"))
      (node (ref "U1") (pin "14") (pinfunction "P212/EXTAL_14") (pintype "passive"))
      (node (ref "X1") (pin "3") (pinfunction "2_3") (pintype "passive"))
    )
    (net (code "44") (name "/P213{slash}XTAL") (class "Default")
      (node (ref "C1") (pin "2") (pinfunction "2_2") (pintype "passive"))
      (node (ref "U1") (pin "13") (pinfunction "P213/XTAL_13") (pintype "passive"))
      (node (ref "X1") (pin "1") (pinfunction "1_1") (pintype "passive"))
    )
    (net (code "45") (name "/P214") (class "Default")
      (node (ref "J5") (pin "4") (pinfunction "4_4") (pintype "passive"))
      (node (ref "U1") (pin "33") (pinfunction "P214_33") (pintype "passive"))
    )
    (net (code "46") (name "/P300{slash}TCK{slash}SWCLK") (class "Default")
      (node (ref "J1") (pin "9") (pinfunction "9_9") (pintype "passive"))
      (node (ref "R21") (pin "1") (pinfunction "1_1") (pintype "passive"))
      (node (ref "U1") (pin "50") (pinfunction "P300/TCK/SWCLK_50") (pintype "passive"))
    )
    (net (code "47") (name "/P301") (class "Default")
      (node (ref "J5") (pin "20") (pinfunction "20_20") (pintype "passive"))
      (node (ref "U1") (pin "49") (pinfunction "P301_49") (pintype "passive"))
    )
    (net (code "48") (name "/P302") (class "Default")
      (node (ref "J5") (pin "19") (pinfunction "19_19") (pintype "passive"))
      (node (ref "U1") (pin "48") (pinfunction "P302_48") (pintype "passive"))
    )
    (net (code "49") (name "/P303") (class "Default")
      (node (ref "J5") (pin "18") (pinfunction "18_18") (pintype "passive"))
      (node (ref "U1") (pin "47") (pinfunction "P303_47") (pintype "passive"))
    )
    (net (code "50") (name "/P304") (class "Default")
      (node (ref "J5") (pin "14") (pinfunction "14_14") (pintype "passive"))
      (node (ref "J9") (pin "7") (pinfunction "7_7") (pintype "passive"))
      (node (ref "U1") (pin "44") (pinfunction "P304_44") (pintype "passive"))
    )
    (net (code "51") (name "/P305") (class "Default")
      (node (ref "J5") (pin "13") (pinfunction "13_13") (pintype "passive"))
      (node (ref "U1") (pin "43") (pinfunction "P305_43") (pintype "passive"))
    )
    (net (code "52") (name "/P306") (class "Default")
      (node (ref "J5") (pin "12") (pinfunction "12_12") (pintype "passive"))
      (node (ref "U1") (pin "42") (pinfunction "P306_42") (pintype "passive"))
    )
    (net (code "53") (name "/P307") (class "Default")
      (node (ref "J5") (pin "11") (pinfunction "11_11") (pintype "passive"))
      (node (ref "U1") (pin "41") (pinfunction "P307_41") (pintype "passive"))
    )
    (net (code "54") (name "/P400") (class "Default")
      (node (ref "J3") (pin "1") (pinfunction "1_1") (pintype "passive"))
      (node (ref "U1") (pin "1") (pinfunction "P400_1") (pintype "passive"))
    )
    (net (code "55") (name "/P401") (class "Default")
      (node (ref "J3") (pin "2") (pinfunction "2_2") (pintype "passive"))
      (node (ref "U1") (pin "2") (pinfunction "P401_2") (pintype "passive"))
    )
    (net (code "56") (name "/P402") (class "Default")
      (node (ref "J3") (pin "3") (pinfunction "3_3") (pintype "passive"))
      (node (ref "J9") (pin "9") (pinfunction "9_9") (pintype "passive"))
      (node (ref "U1") (pin "3") (pinfunction "P402_3") (pintype "passive"))
    )
    (net (code "57") (name "/P403") (class "Default")
      (node (ref "J3") (pin "4") (pinfunction "4_4") (pintype "passive"))
      (node (ref "U1") (pin "4") (pinfunction "P403_4") (pintype "passive"))
    )
    (net (code "58") (name "/P404") (class "Default")
      (node (ref "J3") (pin "5") (pinfunction "5_5") (pintype "passive"))
      (node (ref "J9") (pin "8") (pinfunction "8_8") (pintype "passive"))
      (node (ref "U1") (pin "5") (pinfunction "P404_5") (pintype "passive"))
    )
    (net (code "59") (name "/P405") (class "Default")
      (node (ref "J3") (pin "6") (pinfunction "6_6") (pintype "passive"))
      (node (ref "J9") (pin "10") (pinfunction "10_10") (pintype "passive"))
      (node (ref "U1") (pin "6") (pinfunction "P405_6") (pintype "passive"))
    )
    (net (code "60") (name "/P406") (class "Default")
      (node (ref "J3") (pin "7") (pinfunction "7_7") (pintype "passive"))
      (node (ref "U1") (pin "7") (pinfunction "P406_7") (pintype "passive"))
    )
    (net (code "61") (name "/P407") (class "Default")
      (node (ref "C67") (pin "1") (pinfunction "1_1") (pintype "passive"))
      (node (ref "J3") (pin "20") (pinfunction "20_20") (pintype "passive"))
      (node (ref "RA2") (pin "1") (pinfunction "1_1") (pintype "passive"))
      (node (ref "RA2") (pin "2") (pinfunction "2_2") (pintype "passive"))
      (node (ref "RA2") (pin "3") (pinfunction "3_3") (pintype "passive"))
      (node (ref "U1") (pin "25") (pinfunction "P407_25") (pintype "passive"))
    )
    (net (code "62") (name "/P408") (class "Default")
      (node (ref "J3") (pin "19") (pinfunction "19_19") (pintype "passive"))
      (node (ref "U1") (pin "24") (pinfunction "P408_24") (pintype "passive"))
    )
    (net (code "63") (name "/P409") (class "Default")
      (node (ref "J3") (pin "18") (pinfunction "18_18") (pintype "passive"))
      (node (ref "U1") (pin "23") (pinfunction "P409_23") (pintype "passive"))
    )
    (net (code "64") (name "/P410") (class "Default")
      (node (ref "J3") (pin "17") (pinfunction "17_17") (pintype "passive"))
      (node (ref "U1") (pin "22") (pinfunction "P410_22") (pintype "passive"))
    )
    (net (code "65") (name "/P411") (class "Default")
      (node (ref "J3") (pin "16") (pinfunction "16_16") (pintype "passive"))
      (node (ref "U1") (pin "21") (pinfunction "P411_21") (pintype "passive"))
    )
    (net (code "66") (name "/P412") (class "Default")
      (node (ref "J3") (pin "15") (pinfunction "15_15") (pintype "passive"))
      (node (ref "U1") (pin "20") (pinfunction "P412_20") (pintype "passive"))
    )
    (net (code "67") (name "/P413") (class "Default")
      (node (ref "J3") (pin "14") (pinfunction "14_14") (pintype "passive"))
      (node (ref "U1") (pin "19") (pinfunction "P413_19") (pintype "passive"))
    )
    (net (code "68") (name "/P414") (class "Default")
      (node (ref "J3") (pin "13") (pinfunction "13_13") (pintype "passive"))
      (node (ref "U1") (pin "18") (pinfunction "P414_18") (pintype "passive"))
    )
    (net (code "69") (name "/P415") (class "Default")
      (node (ref "C41") (pin "2") (pinfunction "2_2") (pintype "passive"))
      (node (ref "J3") (pin "12") (pinfunction "12_12") (pintype "passive"))
      (node (ref "R6") (pin "1") (pinfunction "1_1") (pintype "passive"))
      (node (ref "S2") (pin "1") (pinfunction "1_1") (pintype "passive"))
      (node (ref "S2") (pin "3") (pinfunction "3_3") (pintype "passive"))
      (node (ref "U1") (pin "17") (pinfunction "P415_17") (pintype "passive"))
    )
    (net (code "70") (name "/P500") (class "Default")
      (node (ref "J6") (pin "20") (pinfunction "20_20") (pintype "passive"))
      (node (ref "U1") (pin "76") (pinfunction "P500_76") (pintype "passive"))
    )
    (net (code "71") (name "/P501") (class "Default")
      (node (ref "J6") (pin "19") (pinfunction "19_19") (pintype "passive"))
      (node (ref "U1") (pin "77") (pinfunction "P501_77") (pintype "passive"))
    )
    (net (code "72") (name "/P502") (class "Default")
      (node (ref "J6") (pin "18") (pinfunction "18_18") (pintype "passive"))
      (node (ref "U1") (pin "78") (pinfunction "P502_78") (pintype "passive"))
    )
    (net (code "73") (name "/P503") (class "Default")
      (node (ref "J6") (pin "17") (pinfunction "17_17") (pintype "passive"))
      (node (ref "U1") (pin "79") (pinfunction "P503_79") (pintype "passive"))
    )
    (net (code "74") (name "/P504") (class "Default")
      (node (ref "J6") (pin "16") (pinfunction "16_16") (pintype "passive"))
      (node (ref "U1") (pin "80") (pinfunction "P504_80") (pintype "passive"))
    )
    (net (code "75") (name "/P508") (class "Default")
      (node (ref "J6") (pin "15") (pinfunction "15_15") (pintype "passive"))
      (node (ref "U1") (pin "81") (pinfunction "P508_81") (pintype "passive"))
    )
    (net (code "76") (name "/P600") (class "Default")
      (node (ref "J4") (pin "9") (pinfunction "9_9") (pintype "passive"))
      (node (ref "U1") (pin "67") (pinfunction "P600_67") (pintype "passive"))
    )
    (net (code "77") (name "/P601") (class "Default")
      (node (ref "J4") (pin "10") (pinfunction "10_10") (pintype "passive"))
      (node (ref "U1") (pin "66") (pinfunction "P601_66") (pintype "passive"))
    )
    (net (code "78") (name "/P602") (class "Default")
      (node (ref "J4") (pin "11") (pinfunction "11_11") (pintype "passive"))
      (node (ref "U1") (pin "65") (pinfunction "P602_65") (pintype "passive"))
    )
    (net (code "79") (name "/P608") (class "Default")
      (node (ref "J4") (pin "15") (pinfunction "15_15") (pintype "passive"))
      (node (ref "U1") (pin "59") (pinfunction "P608_59") (pintype "passive"))
    )
    (net (code "80") (name "/P609") (class "Default")
      (node (ref "J4") (pin "14") (pinfunction "14_14") (pintype "passive"))
      (node (ref "U1") (pin "60") (pinfunction "P609_60") (pintype "passive"))
    )
    (net (code "81") (name "/P610") (class "Default")
      (node (ref "J4") (pin "13") (pinfunction "13_13") (pintype "passive"))
      (node (ref "U1") (pin "61") (pinfunction "P610_61") (pintype "passive"))
    )
    (net (code "82") (name "/P708") (class "Default")
      (node (ref "J3") (pin "11") (pinfunction "11_11") (pintype "passive"))
      (node (ref "U1") (pin "16") (pinfunction "P708_16") (pintype "passive"))
    )
    (net (code "83") (name "/RESET_MCU") (class "Default")
      (node (ref "C17") (pin "2") (pinfunction "2_2") (pintype "passive"))
      (node (ref "J1") (pin "6") (pinfunction "6_6") (pintype "passive"))
      (node (ref "R7") (pin "1") (pinfunction "1_1") (pintype "passive"))
      (node (ref "S1") (pin "1") (pinfunction "1_1") (pintype "passive"))
      (node (ref "S1") (pin "3") (pinfunction "3_3") (pintype "passive"))
      (node (ref "U1") (pin "38") (pinfunction "RES_38") (pintype "passive"))
      (node (ref "U2") (pin "46") (pinfunction "P102_46") (pintype "passive"))
    )
    (net (code "84") (name "/USB2_N") (class "Default")
      (node (ref "R30") (pin "2") (pinfunction "2_2") (pintype "passive"))
      (node (ref "USB2") (pin "2") (pinfunction "D-/DM_2") (pintype "passive"))
    )
    (net (code "85") (name "/USB2_P") (class "Default")
      (node (ref "R31") (pin "2") (pinfunction "2_2") (pintype "passive"))
      (node (ref "USB2") (pin "3") (pinfunction "D+/DP_3") (pintype "passive"))
    )
    (net (code "86") (name "/USB_JLINK_N") (class "Default")
      (node (ref "U2") (pin "18") (pinfunction "USB_DM_18") (pintype "passive"))
      (node (ref "USB1") (pin "2") (pinfunction "D-/DM_2") (pintype "passive"))
    )
    (net (code "87") (name "/USB_JLINK_P") (class "Default")
      (node (ref "U2") (pin "19") (pinfunction "USB_DP_19") (pintype "passive"))
      (node (ref "USB1") (pin "3") (pinfunction "D+/DP_3") (pintype "passive"))
    )
    (net (code "88") (name "/USB_MCU_N") (class "Default")
      (node (ref "FL1") (pin "1") (pinfunction "1_1") (pintype "passive"))
      (node (ref "U1") (pin "27") (pinfunction "USB_DM_27") (pintype "passive"))
    )
    (net (code "89") (name "/USB_MCU_P") (class "Default")
      (node (ref "FL1") (pin "4") (pinfunction "4_4") (pintype "passive"))
      (node (ref "U1") (pin "28") (pinfunction "USB_DP_28") (pintype "passive"))
    )
    (net (code "90") (name "/VCL") (class "Default")
      (node (ref "C15") (pin "2") (pinfunction "2_2") (pintype "passive"))
      (node (ref "U1") (pin "64") (pinfunction "VCL_64") (pintype "passive"))
    )
    (net (code "91") (name "/VCL0") (class "Default")
      (node (ref "C14") (pin "2") (pinfunction "2_2") (pintype "passive"))
      (node (ref "U1") (pin "9") (pinfunction "VCL0_9") (pintype "passive"))
    )
    (net (code "92") (name "/XCIN") (class "Default")
      (node (ref "C3") (pin "1") (pinfunction "1_1") (pintype "passive"))
      (node (ref "U1") (pin "10") (pinfunction "XCIN_10") (pintype "passive"))
      (node (ref "X2") (pin "1") (pinfunction "1_1") (pintype "passive"))
    )
    (net (code "93") (name "/XOUT") (class "Default")
      (node (ref "C4") (pin "1") (pinfunction "1_1") (pintype "passive"))
      (node (ref "U1") (pin "11") (pinfunction "XCOUT_11") (pintype "passive"))
      (node (ref "X2") (pin "2") (pinfunction "2_2") (pintype "passive"))
    )
    (net (code "94") (name "3V3_JLINK") (class "Default")
      (node (ref "C10") (pin "2") (pinfunction "2_2") (pintype "passive"))
      (node (ref "C11") (pin "2") (pinfunction "2_2") (pintype "passive"))
      (node (ref "C12") (pin "2") (pinfunction "2_2") (pintype "passive"))
      (node (ref "C13") (pin "2") (pinfunction "2_2") (pintype "passive"))
      (node (ref "C32") (pin "2") (pinfunction "2_2") (pintype "passive"))
      (node (ref "C33") (pin "1") (pinfunction "1_1") (pintype "passive"))
      (node (ref "C5") (pin "2") (pinfunction "2_2") (pintype "passive"))
      (node (ref "C51") (pin "2") (pinfunction "2_2") (pintype "passive"))
      (node (ref "C52") (pin "2") (pinfunction "2_2") (pintype "passive"))
      (node (ref "C53") (pin "2") (pinfunction "2_2") (pintype "passive"))
      (node (ref "C54") (pin "2") (pinfunction "2_2") (pintype "passive"))
      (node (ref "C55") (pin "2") (pinfunction "2_2") (pintype "passive"))
      (node (ref "C56") (pin "2") (pinfunction "2_2") (pintype "passive"))
      (node (ref "C57") (pin "2") (pinfunction "2_2") (pintype "passive"))
      (node (ref "C6") (pin "2") (pinfunction "2_2") (pintype "passive"))
      (node (ref "C62") (pin "2") (pinfunction "2_2") (pintype "passive"))
      (node (ref "C63") (pin "2") (pinfunction "2_2") (pintype "passive"))
      (node (ref "C64") (pin "2") (pinfunction "2_2") (pintype "passive"))
      (node (ref "C65") (pin "2") (pinfunction "2_2") (pintype "passive"))
      (node (ref "C69") (pin "2") (pinfunction "2_2") (pintype "passive"))
      (node (ref "C7") (pin "2") (pinfunction "2_2") (pintype "passive"))
      (node (ref "C8") (pin "2") (pinfunction "2_2") (pintype "passive"))
      (node (ref "C9") (pin "2") (pinfunction "2_2") (pintype "passive"))
      (node (ref "J1") (pin "1") (pinfunction "1_1") (pintype "passive"))
      (node (ref "J2") (pin "1") (pinfunction "1_1") (pintype "passive"))
      (node (ref "J3") (pin "8") (pinfunction "8_8") (pintype "passive"))
      (node (ref "J5") (pin "16") (pinfunction "16_16") (pintype "passive"))
      (node (ref "J6") (pin "10") (pinfunction "10_10") (pintype "passive"))
      (node (ref "J7") (pin "6") (pinfunction "6_6") (pintype "passive"))
      (node (ref "J9") (pin "12") (pinfunction "12_12") (pintype "passive"))
      (node (ref "POT1") (pin "1") (pinfunction "CCW_1") (pintype "passive"))
      (node (ref "R10") (pin "2") (pinfunction "2_2") (pintype "passive"))
      (node (ref "R11") (pin "2") (pinfunction "2_2") (pintype "passive"))
      (node (ref "R3") (pin "1") (pinfunction "1_1") (pintype "passive"))
      (node (ref "R6") (pin "2") (pinfunction "2_2") (pintype "passive"))
      (node (ref "R7") (pin "2") (pinfunction "2_2") (pintype "passive"))
      (node (ref "R8") (pin "2") (pinfunction "2_2") (pintype "passive"))
      (node (ref "U1") (pin "15") (pinfunction "VCC_1_15") (pintype "passive"))
      (node (ref "U1") (pin "29") (pinfunction "VCC_USB_29") (pintype "passive"))
      (node (ref "U1") (pin "46") (pinfunction "VCC_2_46") (pintype "passive"))
      (node (ref "U1") (pin "62") (pinfunction "VCC_3_62") (pintype "passive"))
      (node (ref "U1") (pin "8") (pinfunction "VBATT_8") (pintype "passive"))
      (node (ref "U1") (pin "82") (pinfunction "VCC_4_82") (pintype "passive"))
      (node (ref "U1") (pin "87") (pinfunction "VREFH_87") (pintype "passive"))
      (node (ref "U1") (pin "88") (pinfunction "AVCC0_88") (pintype "passive"))
      (node (ref "U1") (pin "91") (pinfunction "VREFH0_91") (pintype "passive"))
      (node (ref "U2") (pin "11") (pinfunction "VCC_1_11") (pintype "passive"))
      (node (ref "U2") (pin "20") (pinfunction "VCC_USB_20") (pintype "passive"))
      (node (ref "U2") (pin "21") (pinfunction "VCC_USB_LDO_21") (pintype "passive"))
      (node (ref "U2") (pin "39") (pinfunction "VCC_2_39") (pintype "passive"))
      (node (ref "U2") (pin "56") (pinfunction "AVCC0_56") (pintype "passive"))
      (node (ref "U4") (pin "2") (pinfunction "VOUT_2") (pintype "passive"))
      (node (ref "U4") (pin "4") (pinfunction "VOUT_4") (pintype "passive"))
    )
    (net (code "95") (name "GND") (class "Default")
      (node (ref "C1") (pin "1") (pinfunction "1_1") (pintype "passive"))
      (node (ref "C10") (pin "1") (pinfunction "1_1") (pintype "passive"))
      (node (ref "C11") (pin "1") (pinfunction "1_1") (pintype "passive"))
      (node (ref "C12") (pin "1") (pinfunction "1_1") (pintype "passive"))
      (node (ref "C13") (pin "1") (pinfunction "1_1") (pintype "passive"))
      (node (ref "C14") (pin "1") (pinfunction "1_1") (pintype "passive"))
      (node (ref "C15") (pin "1") (pinfunction "1_1") (pintype "passive"))
      (node (ref "C16") (pin "2") (pinfunction "2_2") (pintype "passive"))
      (node (ref "C17") (pin "1") (pinfunction "1_1") (pintype "passive"))
      (node (ref "C2") (pin "1") (pinfunction "1_1") (pintype "passive"))
      (node (ref "C3") (pin "2") (pinfunction "2_2") (pintype "passive"))
      (node (ref "C30") (pin "1") (pinfunction "1_1") (pintype "passive"))
      (node (ref "C31") (pin "2") (pinfunction "2_2") (pintype "passive"))
      (node (ref "C32") (pin "1") (pinfunction "1_1") (pintype "passive"))
      (node (ref "C33") (pin "2") (pinfunction "2_2") (pintype "passive"))
      (node (ref "C4") (pin "2") (pinfunction "2_2") (pintype "passive"))
      (node (ref "C41") (pin "1") (pinfunction "1_1") (pintype "passive"))
      (node (ref "C42") (pin "1") (pinfunction "1_1") (pintype "passive"))
      (node (ref "C5") (pin "1") (pinfunction "1_1") (pintype "passive"))
      (node (ref "C50") (pin "2") (pinfunction "2_2") (pintype "passive"))
      (node (ref "C51") (pin "1") (pinfunction "1_1") (pintype "passive"))
      (node (ref "C52") (pin "1") (pinfunction "1_1") (pintype "passive"))
      (node (ref "C53") (pin "1") (pinfunction "1_1") (pintype "passive"))
      (node (ref "C54") (pin "1") (pinfunction "1_1") (pintype "passive"))
      (node (ref "C55") (pin "1") (pinfunction "1_1") (pintype "passive"))
      (node (ref "C56") (pin "1") (pinfunction "1_1") (pintype "passive"))
      (node (ref "C57") (pin "1") (pinfunction "1_1") (pintype "passive"))
      (node (ref "C58") (pin "1") (pinfunction "1_1") (pintype "passive"))
      (node (ref "C6") (pin "1") (pinfunction "1_1") (pintype "passive"))
      (node (ref "C60") (pin "2") (pinfunction "2_2") (pintype "passive"))
      (node (ref "C61") (pin "2") (pinfunction "2_2") (pintype "passive"))
      (node (ref "C62") (pin "1") (pinfunction "1_1") (pintype "passive"))
      (node (ref "C63") (pin "1") (pinfunction "1_1") (pintype "passive"))
      (node (ref "C64") (pin "1") (pinfunction "1_1") (pintype "passive"))
      (node (ref "C65") (pin "1") (pinfunction "1_1") (pintype "passive"))
      (node (ref "C67") (pin "2") (pinfunction "2_2") (pintype "passive"))
      (node (ref "C69") (pin "1") (pinfunction "1_1") (pintype "passive"))
      (node (ref "C7") (pin "1") (pinfunction "1_1") (pintype "passive"))
      (node (ref "C8") (pin "1") (pinfunction "1_1") (pintype "passive"))
      (node (ref "C9") (pin "1") (pinfunction "1_1") (pintype "passive"))
      (node (ref "J1") (pin "2") (pinfunction "2_2") (pintype "passive"))
      (node (ref "J1") (pin "3") (pinfunction "3_3") (pintype "passive"))
      (node (ref "J1") (pin "5") (pinfunction "5_5") (pintype "passive"))
      (node (ref "J2") (pin "5") (pinfunction "5_5") (pintype "passive"))
      (node (ref "J3") (pin "9") (pinfunction "9_9") (pintype "passive"))
      (node (ref "J5") (pin "15") (pinfunction "15_15") (pintype "passive"))
      (node (ref "J6") (pin "11") (pinfunction "11_11") (pintype "passive"))
      (node (ref "J7") (pin "5") (pinfunction "5_5") (pintype "passive"))
      (node (ref "J9") (pin "11") (pinfunction "11_11") (pintype "passive"))
      (node (ref "J9") (pin "5") (pinfunction "5_5") (pintype "passive"))
      (node (ref "J9") (pin "6") (pinfunction "6_6") (pintype "passive"))
      (node (ref "LED1") (pin "2") (pinfunction "K_YG_2") (pintype "passive"))
      (node (ref "LED1") (pin "4") (pinfunction "K_R_4") (pintype "passive"))
      (node (ref "LED2") (pin "1") (pinfunction "K2_1") (pintype "passive"))
      (node (ref "POT1") (pin "3") (pinfunction "CW_3") (pintype "passive"))
      (node (ref "R9") (pin "1") (pinfunction "1_1") (pintype "passive"))
      (node (ref "RA1") (pin "7") (pinfunction "7_7") (pintype "passive"))
      (node (ref "RA1") (pin "8") (pinfunction "8_8") (pintype "passive"))
      (node (ref "RA2") (pin "5") (pinfunction "5_5") (pintype "passive"))
      (node (ref "RA2") (pin "6") (pinfunction "6_6") (pintype "passive"))
      (node (ref "S1") (pin "2") (pinfunction "2_2") (pintype "passive"))
      (node (ref "S1") (pin "4") (pinfunction "4_4") (pintype "passive"))
      (node (ref "S2") (pin "2") (pinfunction "2_2") (pintype "passive"))
      (node (ref "S2") (pin "4") (pinfunction "4_4") (pintype "passive"))
      (node (ref "U1") (pin "12") (pinfunction "VSS_1_12") (pintype "passive"))
      (node (ref "U1") (pin "26") (pinfunction "VSS_USB_26") (pintype "passive"))
      (node (ref "U1") (pin "45") (pinfunction "VSS_2_45") (pintype "passive"))
      (node (ref "U1") (pin "63") (pinfunction "VSS_3_63") (pintype "passive"))
      (node (ref "U1") (pin "83") (pinfunction "VSS_4_83") (pintype "passive"))
      (node (ref "U1") (pin "86") (pinfunction "VREFL_86") (pintype "passive"))
      (node (ref "U1") (pin "89") (pinfunction "AVSS0_89") (pintype "passive"))
      (node (ref "U1") (pin "90") (pinfunction "VREFL0_90") (pintype "passive"))
      (node (ref "U2") (pin "17") (pinfunction "VSS_USB_17") (pintype "passive"))
      (node (ref "U2") (pin "40") (pinfunction "VSS_2_40") (pintype "passive"))
      (node (ref "U2") (pin "57") (pinfunction "AVSS0_57") (pintype "passive"))
      (node (ref "U2") (pin "8") (pinfunction "VSS_1_8") (pintype "passive"))
      (node (ref "U4") (pin "1") (pinfunction "GND_1") (pintype "passive"))
      (node (ref "USB1") (pin "5") (pinfunction "GND_5") (pintype "passive"))
      (node (ref "USB2") (pin "5") (pinfunction "GND_5") (pintype "passive"))
      (node (ref "X1") (pin "2") (pinfunction "GND_2") (pintype "power_in"))
      (node (ref "X1") (pin "4") (pinfunction "GND_4") (pintype "power_in"))
    )
    (net (code "96") (name "Net-(C60-Pad1)") (class "Default")
      (node (ref "C60") (pin "1") (pinfunction "1_1") (pintype "passive"))
      (node (ref "FL1") (pin "2") (pinfunction "2_2") (pintype "passive"))
      (node (ref "R30") (pin "1") (pinfunction "1_1") (pintype "passive"))
    )
    (net (code "97") (name "Net-(C61-Pad1)") (class "Default")
      (node (ref "C61") (pin "1") (pinfunction "1_1") (pintype "passive"))
      (node (ref "FL1") (pin "3") (pinfunction "3_3") (pintype "passive"))
      (node (ref "R31") (pin "1") (pinfunction "1_1") (pintype "passive"))
    )
    (net (code "98") (name "Net-(D1-K)") (class "Default")
      (node (ref "C30") (pin "2") (pinfunction "2_2") (pintype "passive"))
      (node (ref "C31") (pin "1") (pinfunction "1_1") (pintype "passive"))
      (node (ref "D1") (pin "1") (pinfunction "K_1") (pintype "passive"))
      (node (ref "U4") (pin "3") (pinfunction "VIN_3") (pintype "passive"))
    )
    (net (code "99") (name "Net-(J8-Pad2)") (class "Default")
      (node (ref "J8") (pin "2") (pinfunction "2_2") (pintype "passive"))
      (node (ref "R8") (pin "1") (pinfunction "1_1") (pintype "passive"))
    )
    (net (code "100") (name "Net-(J8-Pad3)") (class "Default")
      (node (ref "J8") (pin "3") (pinfunction "3_3") (pintype "passive"))
      (node (ref "R9") (pin "2") (pinfunction "2_2") (pintype "passive"))
    )
    (net (code "101") (name "Net-(LED1-A_R)") (class "Default")
      (node (ref "LED1") (pin "3") (pinfunction "A_R_3") (pintype "passive"))
      (node (ref "R4") (pin "2") (pinfunction "2_2") (pintype "passive"))
    )
    (net (code "102") (name "Net-(LED1-A_YG)") (class "Default")
      (node (ref "LED1") (pin "1") (pinfunction "A_YG_1") (pintype "passive"))
      (node (ref "R3") (pin "2") (pinfunction "2_2") (pintype "passive"))
    )
    (net (code "103") (name "Net-(LED2-A2)") (class "Default")
      (node (ref "LED2") (pin "2") (pinfunction "A2_2") (pintype "passive"))
      (node (ref "R5") (pin "2") (pinfunction "2_2") (pintype "passive"))
    )
    (net (code "104") (name "Net-(U2-P000)") (class "Default")
      (node (ref "R21") (pin "2") (pinfunction "2_2") (pintype "passive"))
      (node (ref "U2") (pin "64") (pinfunction "P000_64") (pintype "passive"))
    )
    (net (code "105") (name "Net-(U2-P100)") (class "Default")
      (node (ref "R20") (pin "1") (pinfunction "1_1") (pintype "passive"))
      (node (ref "U2") (pin "48") (pinfunction "P100_48") (pintype "passive"))
    )
    (net (code "106") (name "Net-(U2-VCL)") (class "Default")
      (node (ref "C50") (pin "1") (pinfunction "1_1") (pintype "passive"))
      (node (ref "U2") (pin "5") (pinfunction "VCL_5") (pintype "passive"))
    )
    (net (code "107") (name "Net-(USB2-VBUS)") (class "Default")
      (node (ref "RA2") (pin "7") (pinfunction "7_7") (pintype "passive"))
      (node (ref "RA2") (pin "8") (pinfunction "8_8") (pintype "passive"))
      (node (ref "USB2") (pin "1") (pinfunction "VBUS_1") (pintype "passive"))
    )
    (net (code "108") (name "unconnected-(J1-Pad4)") (class "Default")
      (node (ref "J1") (pin "4") (pinfunction "4_4") (pintype "passive+no_connect"))
    )
    (net (code "109") (name "unconnected-(J2-Pad6)") (class "Default")
      (node (ref "J2") (pin "6") (pinfunction "6_6") (pintype "passive+no_connect"))
    )
    (net (code "110") (name "unconnected-(J3-Pad10)") (class "Default")
      (node (ref "J3") (pin "10") (pinfunction "10_10") (pintype "passive+no_connect"))
    )
    (net (code "111") (name "unconnected-(J4-Pad12)") (class "Default")
      (node (ref "J4") (pin "12") (pinfunction "12_12") (pintype "passive+no_connect"))
    )
    (net (code "112") (name "unconnected-(J5-Pad5)") (class "Default")
      (node (ref "J5") (pin "5") (pinfunction "5_5") (pintype "passive+no_connect"))
    )
    (net (code "113") (name "unconnected-(J5-Pad17)") (class "Default")
      (node (ref "J5") (pin "17") (pinfunction "17_17") (pintype "passive+no_connect"))
    )
    (net (code "114") (name "unconnected-(J6-Pad12)") (class "Default")
      (node (ref "J6") (pin "12") (pinfunction "12_12") (pintype "passive+no_connect"))
    )
    (net (code "115") (name "unconnected-(J8-Pad4)") (class "Default")
      (node (ref "J8") (pin "4") (pinfunction "4_4") (pintype "passive+no_connect"))
    )
    (net (code "116") (name "unconnected-(RA1-Pad1)") (class "Default")
      (node (ref "RA1") (pin "1") (pinfunction "1_1") (pintype "passive+no_connect"))
    )
    (net (code "117") (name "unconnected-(RA2-Pad4)") (class "Default")
      (node (ref "RA2") (pin "4") (pinfunction "4_4") (pintype "passive+no_connect"))
    )
    (net (code "118") (name "unconnected-(U2-P001-Pad63)") (class "Default")
      (node (ref "U2") (pin "63") (pinfunction "P001_63") (pintype "passive+no_connect"))
    )
    (net (code "119") (name "unconnected-(U2-P002-Pad62)") (class "Default")
      (node (ref "U2") (pin "62") (pinfunction "P002_62") (pintype "passive+no_connect"))
    )
    (net (code "120") (name "unconnected-(U2-P003-Pad61)") (class "Default")
      (node (ref "U2") (pin "61") (pinfunction "P003_61") (pintype "passive+no_connect"))
    )
    (net (code "121") (name "unconnected-(U2-P004-Pad60)") (class "Default")
      (node (ref "U2") (pin "60") (pinfunction "P004_60") (pintype "passive+no_connect"))
    )
    (net (code "122") (name "unconnected-(U2-P010{slash}VREFH0-Pad59)") (class "Default")
      (node (ref "U2") (pin "59") (pinfunction "P010/VREFH0_59") (pintype "passive+no_connect"))
    )
    (net (code "123") (name "unconnected-(U2-P011{slash}VREFL0-Pad58)") (class "Default")
      (node (ref "U2") (pin "58") (pinfunction "P011/VREFL0_58") (pintype "passive+no_connect"))
    )
    (net (code "124") (name "unconnected-(U2-P012-Pad55)") (class "Default")
      (node (ref "U2") (pin "55") (pinfunction "P012_55") (pintype "passive+no_connect"))
    )
    (net (code "125") (name "unconnected-(U2-P013-Pad54)") (class "Default")
      (node (ref "U2") (pin "54") (pinfunction "P013_54") (pintype "passive+no_connect"))
    )
    (net (code "126") (name "unconnected-(U2-P014-Pad53)") (class "Default")
      (node (ref "U2") (pin "53") (pinfunction "P014_53") (pintype "passive+no_connect"))
    )
    (net (code "127") (name "unconnected-(U2-P015-Pad52)") (class "Default")
      (node (ref "U2") (pin "52") (pinfunction "P015_52") (pintype "passive+no_connect"))
    )
    (net (code "128") (name "unconnected-(U2-P101-Pad47)") (class "Default")
      (node (ref "U2") (pin "47") (pinfunction "P101_47") (pintype "passive+no_connect"))
    )
    (net (code "129") (name "unconnected-(U2-P104-Pad44)") (class "Default")
      (node (ref "U2") (pin "44") (pinfunction "P104_44") (pintype "passive+no_connect"))
    )
    (net (code "130") (name "unconnected-(U2-P105-Pad43)") (class "Default")
      (node (ref "U2") (pin "43") (pinfunction "P105_43") (pintype "passive+no_connect"))
    )
    (net (code "131") (name "unconnected-(U2-P106-Pad42)") (class "Default")
      (node (ref "U2") (pin "42") (pinfunction "P106_42") (pintype "passive+no_connect"))
    )
    (net (code "132") (name "unconnected-(U2-P107-Pad41)") (class "Default")
      (node (ref "U2") (pin "41") (pinfunction "P107_41") (pintype "passive+no_connect"))
    )
    (net (code "133") (name "unconnected-(U2-P109-Pad34)") (class "Default")
      (node (ref "U2") (pin "34") (pinfunction "P109_34") (pintype "passive+no_connect"))
    )
    (net (code "134") (name "unconnected-(U2-P111-Pad36)") (class "Default")
      (node (ref "U2") (pin "36") (pinfunction "P111_36") (pintype "passive+no_connect"))
    )
    (net (code "135") (name "unconnected-(U2-P112-Pad37)") (class "Default")
      (node (ref "U2") (pin "37") (pinfunction "P112_37") (pintype "passive+no_connect"))
    )
    (net (code "136") (name "unconnected-(U2-P113-Pad38)") (class "Default")
      (node (ref "U2") (pin "38") (pinfunction "P113_38") (pintype "passive+no_connect"))
    )
    (net (code "137") (name "unconnected-(U2-P200-Pad27)") (class "Default")
      (node (ref "U2") (pin "27") (pinfunction "P200_27") (pintype "passive+no_connect"))
    )
    (net (code "138") (name "unconnected-(U2-P201{slash}MD-Pad26)") (class "Default")
      (node (ref "U2") (pin "26") (pinfunction "P201/MD_26") (pintype "passive+no_connect"))
    )
    (net (code "139") (name "unconnected-(U2-P204-Pad24)") (class "Default")
      (node (ref "U2") (pin "24") (pinfunction "P204_24") (pintype "passive+no_connect"))
    )
    (net (code "140") (name "unconnected-(U2-P205-Pad23)") (class "Default")
      (node (ref "U2") (pin "23") (pinfunction "P205_23") (pintype "passive+no_connect"))
    )
    (net (code "141") (name "unconnected-(U2-P206-Pad22)") (class "Default")
      (node (ref "U2") (pin "22") (pinfunction "P206_22") (pintype "passive+no_connect"))
    )
    (net (code "142") (name "unconnected-(U2-P212{slash}EXTAL-Pad10)") (class "Default")
      (node (ref "U2") (pin "10") (pinfunction "P212/EXTAL_10") (pintype "passive+no_connect"))
    )
    (net (code "143") (name "unconnected-(U2-P213{slash}XTAL-Pad9)") (class "Default")
      (node (ref "U2") (pin "9") (pinfunction "P213/XTAL_9") (pintype "passive+no_connect"))
    )
    (net (code "144") (name "unconnected-(U2-P214{slash}XCOUT-Pad7)") (class "Default")
      (node (ref "U2") (pin "7") (pinfunction "P214/XCOUT_7") (pintype "passive+no_connect"))
    )
    (net (code "145") (name "unconnected-(U2-P215{slash}XCIN-Pad6)") (class "Default")
      (node (ref "U2") (pin "6") (pinfunction "P215/XCIN_6") (pintype "passive+no_connect"))
    )
    (net (code "146") (name "unconnected-(U2-P301-Pad31)") (class "Default")
      (node (ref "U2") (pin "31") (pinfunction "P301_31") (pintype "passive+no_connect"))
    )
    (net (code "147") (name "unconnected-(U2-P302-Pad30)") (class "Default")
      (node (ref "U2") (pin "30") (pinfunction "P302_30") (pintype "passive+no_connect"))
    )
    (net (code "148") (name "unconnected-(U2-P303-Pad29)") (class "Default")
      (node (ref "U2") (pin "29") (pinfunction "P303_29") (pintype "passive+no_connect"))
    )
    (net (code "149") (name "unconnected-(U2-P304-Pad28)") (class "Default")
      (node (ref "U2") (pin "28") (pinfunction "P304_28") (pintype "passive+no_connect"))
    )
    (net (code "150") (name "unconnected-(U2-P400-Pad1)") (class "Default")
      (node (ref "U2") (pin "1") (pinfunction "P400_1") (pintype "passive+no_connect"))
    )
    (net (code "151") (name "unconnected-(U2-P401-Pad2)") (class "Default")
      (node (ref "U2") (pin "2") (pinfunction "P401_2") (pintype "passive+no_connect"))
    )
    (net (code "152") (name "unconnected-(U2-P402-Pad3)") (class "Default")
      (node (ref "U2") (pin "3") (pinfunction "P402_3") (pintype "passive+no_connect"))
    )
    (net (code "153") (name "unconnected-(U2-P403-Pad4)") (class "Default")
      (node (ref "U2") (pin "4") (pinfunction "P403_4") (pintype "passive+no_connect"))
    )
    (net (code "154") (name "unconnected-(U2-P408-Pad15)") (class "Default")
      (node (ref "U2") (pin "15") (pinfunction "P408_15") (pintype "passive+no_connect"))
    )
    (net (code "155") (name "unconnected-(U2-P409-Pad14)") (class "Default")
      (node (ref "U2") (pin "14") (pinfunction "P409_14") (pintype "passive+no_connect"))
    )
    (net (code "156") (name "unconnected-(U2-P410-Pad13)") (class "Default")
      (node (ref "U2") (pin "13") (pinfunction "P410_13") (pintype "passive+no_connect"))
    )
    (net (code "157") (name "unconnected-(U2-P411-Pad12)") (class "Default")
      (node (ref "U2") (pin "12") (pinfunction "P411_12") (pintype "passive+no_connect"))
    )
    (net (code "158") (name "unconnected-(U2-P500-Pad49)") (class "Default")
      (node (ref "U2") (pin "49") (pinfunction "P500_49") (pintype "passive+no_connect"))
    )
    (net (code "159") (name "unconnected-(U2-P501-Pad50)") (class "Default")
      (node (ref "U2") (pin "50") (pinfunction "P501_50") (pintype "passive+no_connect"))
    )
    (net (code "160") (name "unconnected-(U2-P502-Pad51)") (class "Default")
      (node (ref "U2") (pin "51") (pinfunction "P502_51") (pintype "passive+no_connect"))
    )
    (net (code "161") (name "unconnected-(USB1-ID-Pad4)") (class "Default")
      (node (ref "USB1") (pin "4") (pinfunction "ID_4") (pintype "passive+no_connect"))
    )
    (net (code "162") (name "unconnected-(USB2-ID-Pad4)") (class "Default")
      (node (ref "USB2") (pin "4") (pinfunction "ID_4") (pintype "passive+no_connect"))
    )
  )
)
